# PCB.net
KiCad netlist of a schematic drawn in EasyEDA Pro
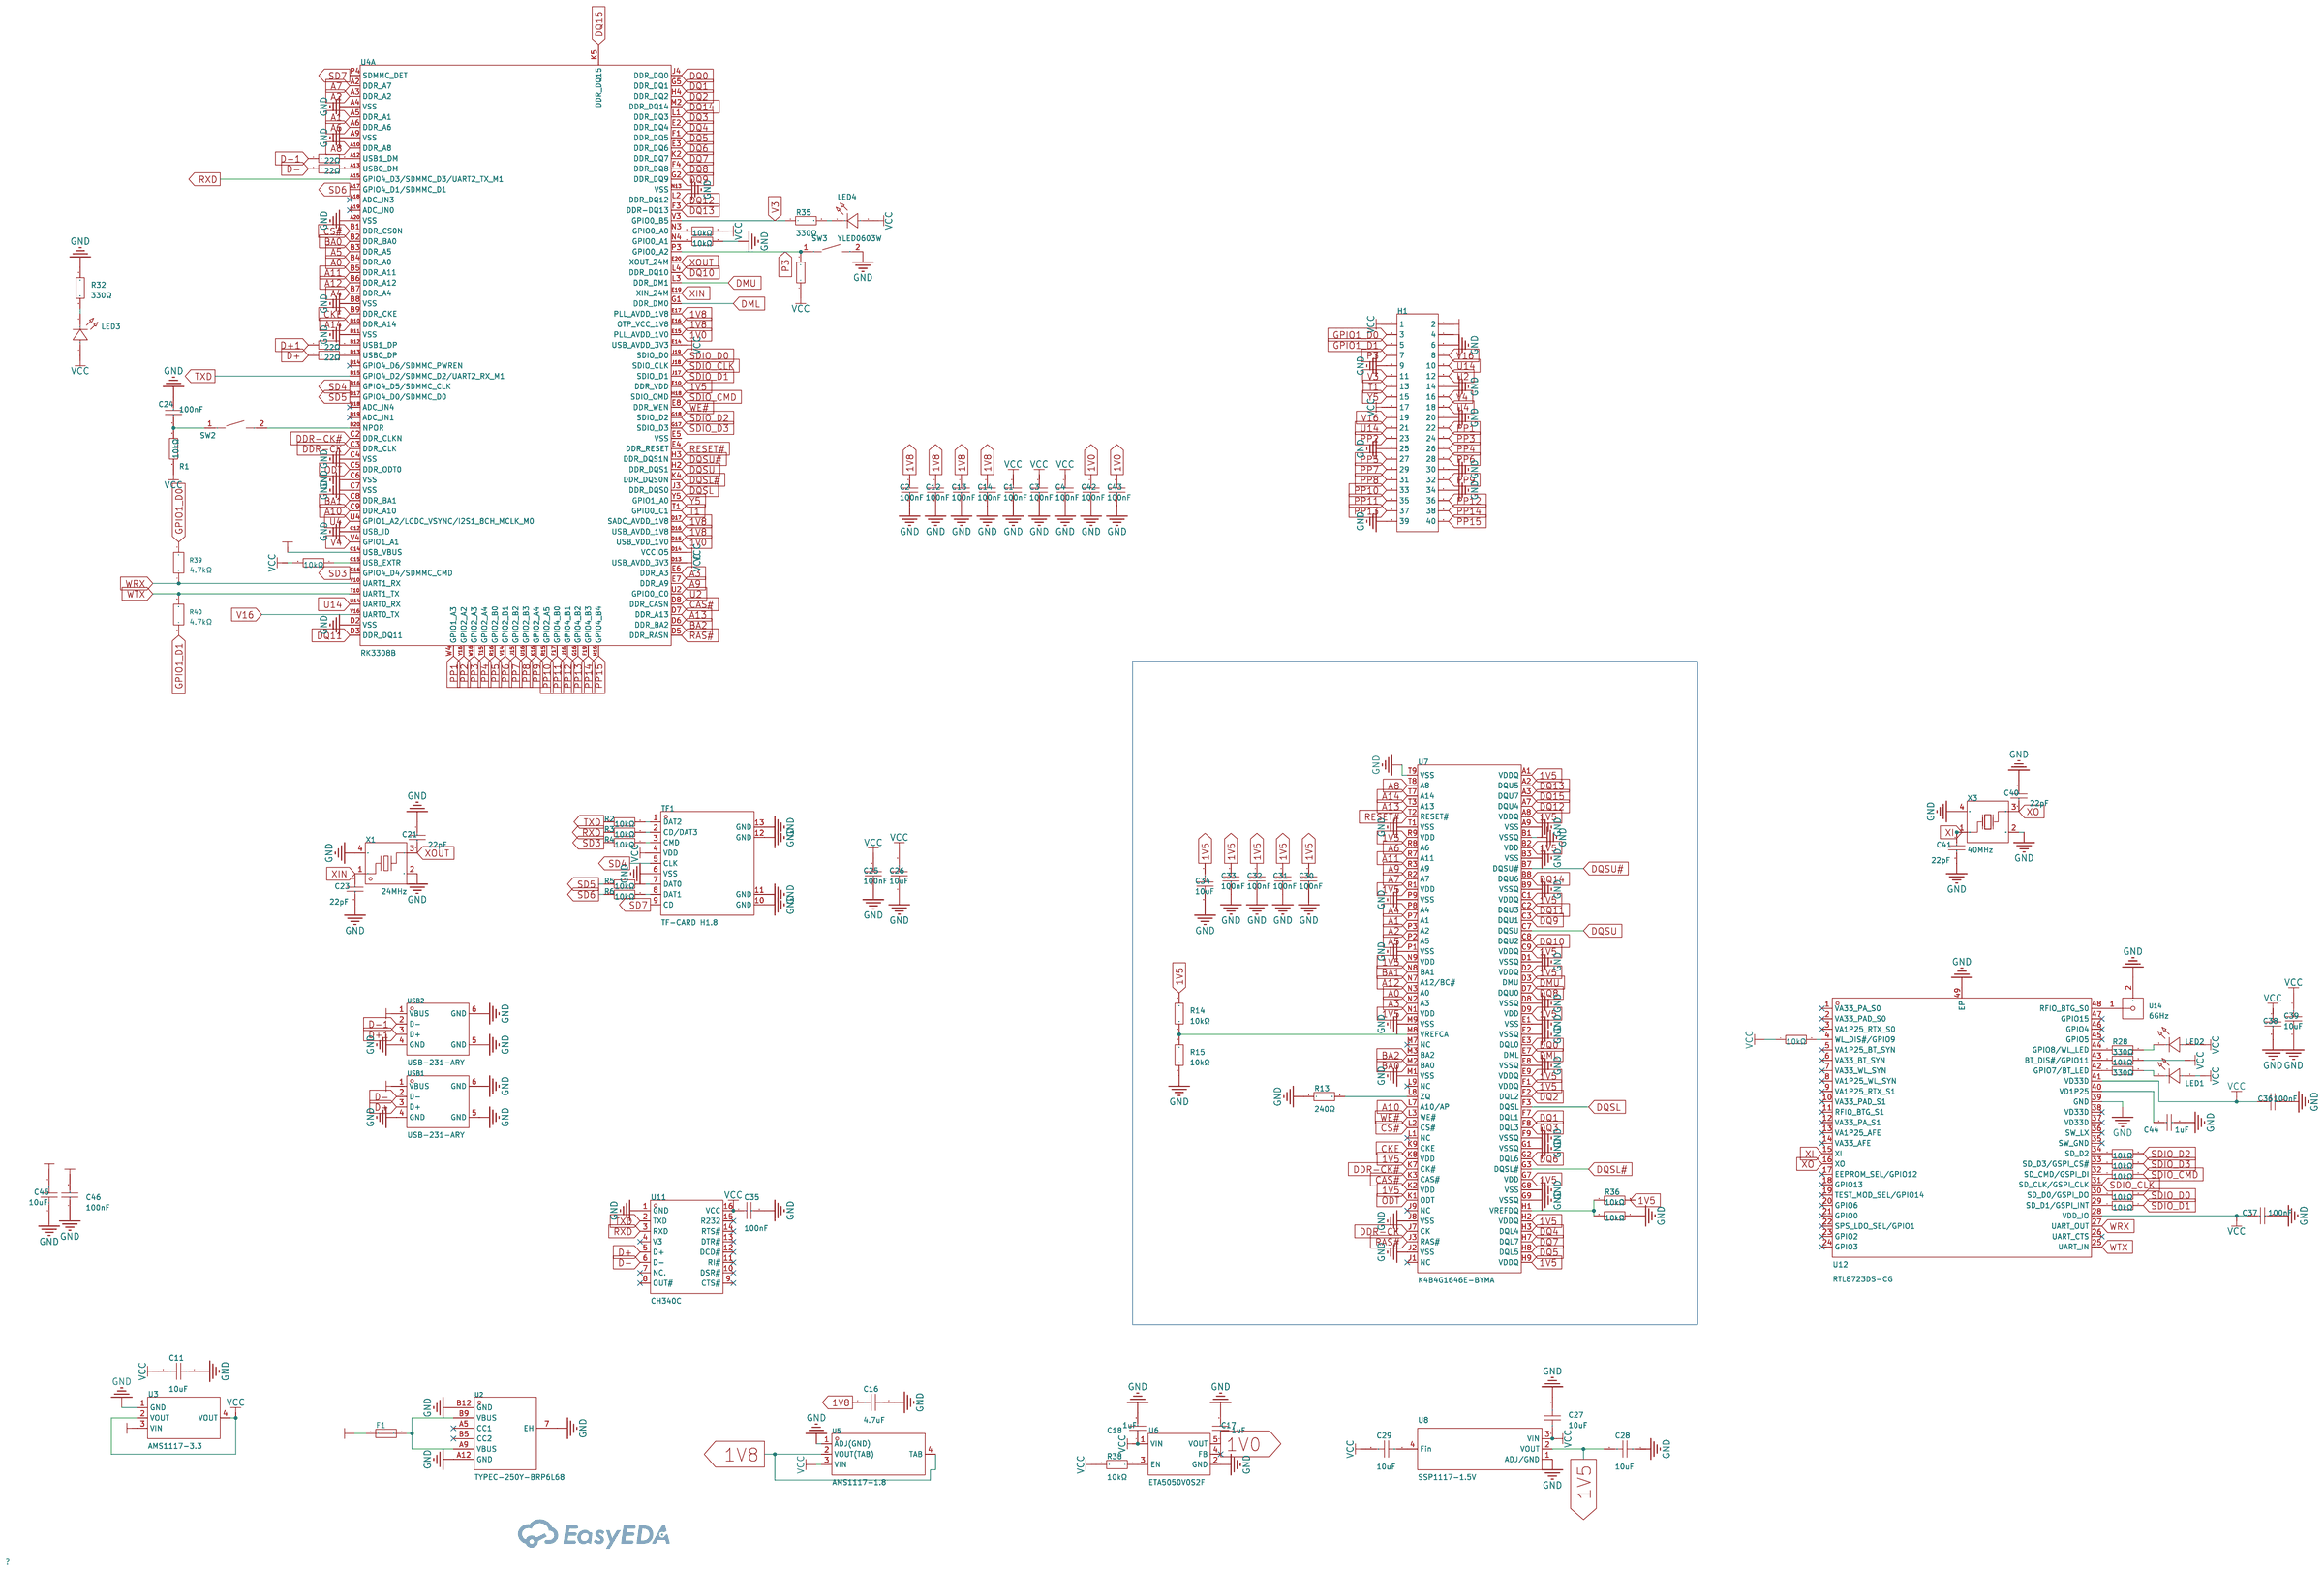
[diagram p0: schematic sheet]

(export (version "E")
  (design (tool "Eeschema 10.0.6"))
  (components
    (comp (ref "C1")
      (value "100nF")
      (footprint "easyedapro:C0603")
      (description "Capacitance:100nF Tolerance:±10% Tolerance:±10% Voltage Rating:50V Temperature Coefficient:-")
      (fields
        (field (name "Manufacturer Part") "CT41G-0603-2X1-50V-0.1uF-K(N)")
        (field (name "Manufacturer") "TORCH(火炬)")
      )
      (libsource (lib "easyedapro") (part "CT41G-0603-2X1-50V-0.1μF-K(N)"))
    )
    (comp (ref "C2")
      (value "100nF")
      (footprint "easyedapro:C0603")
      (description "Capacitance:100nF Tolerance:±10% Tolerance:±10% Voltage Rating:50V Temperature Coefficient:-")
      (fields
        (field (name "Manufacturer Part") "CT41G-0603-2X1-50V-0.1uF-K(N)")
        (field (name "Manufacturer") "TORCH(火炬)")
      )
      (libsource (lib "easyedapro") (part "CT41G-0603-2X1-50V-0.1μF-K(N)"))
    )
    (comp (ref "C3")
      (value "100nF")
      (footprint "easyedapro:C0603")
      (description "Capacitance:100nF Tolerance:±10% Tolerance:±10% Voltage Rating:50V Temperature Coefficient:-")
      (fields
        (field (name "Manufacturer Part") "CT41G-0603-2X1-50V-0.1uF-K(N)")
        (field (name "Manufacturer") "TORCH(火炬)")
      )
      (libsource (lib "easyedapro") (part "CT41G-0603-2X1-50V-0.1μF-K(N)"))
    )
    (comp (ref "C4")
      (value "100nF")
      (footprint "easyedapro:C0603")
      (description "Capacitance:100nF Tolerance:±10% Tolerance:±10% Voltage Rating:50V Temperature Coefficient:-")
      (fields
        (field (name "Manufacturer Part") "CT41G-0603-2X1-50V-0.1uF-K(N)")
        (field (name "Manufacturer") "TORCH(火炬)")
      )
      (libsource (lib "easyedapro") (part "CT41G-0603-2X1-50V-0.1μF-K(N)"))
    )
    (comp (ref "C11")
      (value "10uF")
      (footprint "easyedapro:C0603")
      (description "Capacitance:10uF Tolerance:±10% Tolerance:±10% Voltage Rating:10V Temperature Coefficient:X5R")
      (fields
        (field (name "Manufacturer Part") "CL10A106KP8NNNC")
        (field (name "Manufacturer") "SAMSUNG(三星)")
      )
      (libsource (lib "easyedapro") (part "CL10A106KP8NNNC"))
    )
    (comp (ref "C12")
      (value "100nF")
      (footprint "easyedapro:C0603")
      (description "Capacitance:100nF Tolerance:±10% Tolerance:±10% Voltage Rating:50V Temperature Coefficient:-")
      (fields
        (field (name "Manufacturer Part") "CT41G-0603-2X1-50V-0.1uF-K(N)")
        (field (name "Manufacturer") "TORCH(火炬)")
      )
      (libsource (lib "easyedapro") (part "CT41G-0603-2X1-50V-0.1μF-K(N)"))
    )
    (comp (ref "C13")
      (value "100nF")
      (footprint "easyedapro:C0603")
      (description "Capacitance:100nF Tolerance:±10% Tolerance:±10% Voltage Rating:50V Temperature Coefficient:-")
      (fields
        (field (name "Manufacturer Part") "CT41G-0603-2X1-50V-0.1uF-K(N)")
        (field (name "Manufacturer") "TORCH(火炬)")
      )
      (libsource (lib "easyedapro") (part "CT41G-0603-2X1-50V-0.1μF-K(N)"))
    )
    (comp (ref "C14")
      (value "100nF")
      (footprint "easyedapro:C0603")
      (description "Capacitance:100nF Tolerance:±10% Tolerance:±10% Voltage Rating:50V Temperature Coefficient:-")
      (fields
        (field (name "Manufacturer Part") "CT41G-0603-2X1-50V-0.1uF-K(N)")
        (field (name "Manufacturer") "TORCH(火炬)")
      )
      (libsource (lib "easyedapro") (part "CT41G-0603-2X1-50V-0.1μF-K(N)"))
    )
    (comp (ref "C16")
      (value "4.7uF")
      (footprint "easyedapro:C0603")
      (description "Capacitance:4.7uF Tolerance:±10% Tolerance:±10% Voltage Rating:16V Temperature Coefficient:X5R")
      (fields
        (field (name "Manufacturer Part") "CL10A475KO8NNNC")
        (field (name "Manufacturer") "SAMSUNG(三星)")
      )
      (libsource (lib "easyedapro") (part "CL10A475KO8NNNC"))
    )
    (comp (ref "C17")
      (value "1uF")
      (footprint "easyedapro:C0603")
      (description "Capacitance:1uF Tolerance:±10% Tolerance:±10% Voltage Rating:25V Temperature Coefficient:X7R")
      (fields
        (field (name "Manufacturer Part") "CL10B105KA8NNNC")
        (field (name "Manufacturer") "SAMSUNG(三星)")
      )
      (libsource (lib "easyedapro") (part "CL10B105KA8NNNC"))
    )
    (comp (ref "C18")
      (value "1uF")
      (footprint "easyedapro:C0603")
      (description "Capacitance:1uF Tolerance:±10% Tolerance:±10% Voltage Rating:25V Temperature Coefficient:X7R")
      (fields
        (field (name "Manufacturer Part") "CL10B105KA8NNNC")
        (field (name "Manufacturer") "SAMSUNG(三星)")
      )
      (libsource (lib "easyedapro") (part "CL10B105KA8NNNC"))
    )
    (comp (ref "C21")
      (value "22pF")
      (footprint "easyedapro:C0603")
      (description "Capacitance:22pF Tolerance:±5% Tolerance:±5% Voltage Rating:50V Temperature Coefficient:C0G")
      (fields
        (field (name "Manufacturer Part") "CL10C220JB8NNNC")
        (field (name "Manufacturer") "SAMSUNG(三星)")
      )
      (libsource (lib "easyedapro") (part "CL10C220JB8NNNC"))
    )
    (comp (ref "C23")
      (value "22pF")
      (footprint "easyedapro:C0603")
      (description "Capacitance:22pF Tolerance:±5% Tolerance:±5% Voltage Rating:50V Temperature Coefficient:C0G")
      (fields
        (field (name "Manufacturer Part") "CL10C220JB8NNNC")
        (field (name "Manufacturer") "SAMSUNG(三星)")
      )
      (libsource (lib "easyedapro") (part "CL10C220JB8NNNC"))
    )
    (comp (ref "C24")
      (value "100nF")
      (footprint "easyedapro:C0603")
      (description "Capacitance:100nF Tolerance:±10% Tolerance:±10% Voltage Rating:50V Temperature Coefficient:-")
      (fields
        (field (name "Manufacturer Part") "CT41G-0603-2X1-50V-0.1uF-K(N)")
        (field (name "Manufacturer") "TORCH(火炬)")
      )
      (libsource (lib "easyedapro") (part "CT41G-0603-2X1-50V-0.1μF-K(N)"))
    )
    (comp (ref "C25")
      (value "100nF")
      (footprint "easyedapro:C0603")
      (description "Capacitance:100nF Tolerance:±10% Tolerance:±10% Voltage Rating:50V Temperature Coefficient:-")
      (fields
        (field (name "Manufacturer Part") "CT41G-0603-2X1-50V-0.1uF-K(N)")
        (field (name "Manufacturer") "TORCH(火炬)")
      )
      (libsource (lib "easyedapro") (part "CT41G-0603-2X1-50V-0.1μF-K(N)"))
    )
    (comp (ref "C26")
      (value "10uF")
      (footprint "easyedapro:C0603")
      (description "Capacitance:10uF Tolerance:±10% Tolerance:±10% Voltage Rating:10V Temperature Coefficient:X5R")
      (fields
        (field (name "Manufacturer Part") "CL10A106KP8NNNC")
        (field (name "Manufacturer") "SAMSUNG(三星)")
      )
      (libsource (lib "easyedapro") (part "CL10A106KP8NNNC"))
    )
    (comp (ref "C27")
      (value "10uF")
      (footprint "easyedapro:C0603")
      (description "Capacitance:10uF Tolerance:±10% Tolerance:±10% Voltage Rating:10V Temperature Coefficient:X5R")
      (fields
        (field (name "Manufacturer Part") "CL10A106KP8NNNC")
        (field (name "Manufacturer") "SAMSUNG(三星)")
      )
      (libsource (lib "easyedapro") (part "CL10A106KP8NNNC"))
    )
    (comp (ref "C28")
      (value "10uF")
      (footprint "easyedapro:C0603")
      (description "Capacitance:10uF Tolerance:±10% Tolerance:±10% Voltage Rating:10V Temperature Coefficient:X5R")
      (fields
        (field (name "Manufacturer Part") "CL10A106KP8NNNC")
        (field (name "Manufacturer") "SAMSUNG(三星)")
      )
      (libsource (lib "easyedapro") (part "CL10A106KP8NNNC"))
    )
    (comp (ref "C29")
      (value "10uF")
      (footprint "easyedapro:C0603")
      (description "Capacitance:10uF Tolerance:±10% Tolerance:±10% Voltage Rating:10V Temperature Coefficient:X5R")
      (fields
        (field (name "Manufacturer Part") "CL10A106KP8NNNC")
        (field (name "Manufacturer") "SAMSUNG(三星)")
      )
      (libsource (lib "easyedapro") (part "CL10A106KP8NNNC"))
    )
    (comp (ref "C30")
      (value "100nF")
      (footprint "easyedapro:C0603")
      (description "Capacitance:100nF Tolerance:±10% Tolerance:±10% Voltage Rating:50V Temperature Coefficient:-")
      (fields
        (field (name "Manufacturer Part") "CT41G-0603-2X1-50V-0.1uF-K(N)")
        (field (name "Manufacturer") "TORCH(火炬)")
      )
      (libsource (lib "easyedapro") (part "CT41G-0603-2X1-50V-0.1μF-K(N)"))
    )
    (comp (ref "C31")
      (value "100nF")
      (footprint "easyedapro:C0603")
      (description "Capacitance:100nF Tolerance:±10% Tolerance:±10% Voltage Rating:50V Temperature Coefficient:-")
      (fields
        (field (name "Manufacturer Part") "CT41G-0603-2X1-50V-0.1uF-K(N)")
        (field (name "Manufacturer") "TORCH(火炬)")
      )
      (libsource (lib "easyedapro") (part "CT41G-0603-2X1-50V-0.1μF-K(N)"))
    )
    (comp (ref "C32")
      (value "100nF")
      (footprint "easyedapro:C0603")
      (description "Capacitance:100nF Tolerance:±10% Tolerance:±10% Voltage Rating:50V Temperature Coefficient:-")
      (fields
        (field (name "Manufacturer Part") "CT41G-0603-2X1-50V-0.1uF-K(N)")
        (field (name "Manufacturer") "TORCH(火炬)")
      )
      (libsource (lib "easyedapro") (part "CT41G-0603-2X1-50V-0.1μF-K(N)"))
    )
    (comp (ref "C33")
      (value "100nF")
      (footprint "easyedapro:C0603")
      (description "Capacitance:100nF Tolerance:±10% Tolerance:±10% Voltage Rating:50V Temperature Coefficient:-")
      (fields
        (field (name "Manufacturer Part") "CT41G-0603-2X1-50V-0.1uF-K(N)")
        (field (name "Manufacturer") "TORCH(火炬)")
      )
      (libsource (lib "easyedapro") (part "CT41G-0603-2X1-50V-0.1μF-K(N)"))
    )
    (comp (ref "C34")
      (value "10uF")
      (footprint "easyedapro:C0603")
      (description "Capacitance:10uF Tolerance:±10% Tolerance:±10% Voltage Rating:10V Temperature Coefficient:X5R")
      (fields
        (field (name "Manufacturer Part") "CL10A106KP8NNNC")
        (field (name "Manufacturer") "SAMSUNG(三星)")
      )
      (libsource (lib "easyedapro") (part "CL10A106KP8NNNC"))
    )
    (comp (ref "C35")
      (value "100nF")
      (footprint "easyedapro:C0603")
      (description "Capacitance:100nF Tolerance:±10% Tolerance:±10% Voltage Rating:50V Temperature Coefficient:-")
      (fields
        (field (name "Manufacturer Part") "CT41G-0603-2X1-50V-0.1uF-K(N)")
        (field (name "Manufacturer") "TORCH(火炬)")
      )
      (libsource (lib "easyedapro") (part "CT41G-0603-2X1-50V-0.1μF-K(N)"))
    )
    (comp (ref "C36")
      (value "100nF")
      (footprint "easyedapro:C0603")
      (description "Capacitance:100nF Tolerance:±10% Tolerance:±10% Voltage Rating:50V Temperature Coefficient:-")
      (fields
        (field (name "Manufacturer Part") "CT41G-0603-2X1-50V-0.1uF-K(N)")
        (field (name "Manufacturer") "TORCH(火炬)")
      )
      (libsource (lib "easyedapro") (part "CT41G-0603-2X1-50V-0.1μF-K(N)"))
    )
    (comp (ref "C37")
      (value "100nF")
      (footprint "easyedapro:C0603")
      (description "Capacitance:100nF Tolerance:±10% Tolerance:±10% Voltage Rating:50V Temperature Coefficient:-")
      (fields
        (field (name "Manufacturer Part") "CT41G-0603-2X1-50V-0.1uF-K(N)")
        (field (name "Manufacturer") "TORCH(火炬)")
      )
      (libsource (lib "easyedapro") (part "CT41G-0603-2X1-50V-0.1μF-K(N)"))
    )
    (comp (ref "C38")
      (value "100nF")
      (footprint "easyedapro:C0603")
      (description "Capacitance:100nF Tolerance:±10% Tolerance:±10% Voltage Rating:50V Temperature Coefficient:-")
      (fields
        (field (name "Manufacturer Part") "CT41G-0603-2X1-50V-0.1uF-K(N)")
        (field (name "Manufacturer") "TORCH(火炬)")
      )
      (libsource (lib "easyedapro") (part "CT41G-0603-2X1-50V-0.1μF-K(N)"))
    )
    (comp (ref "C39")
      (value "10uF")
      (footprint "easyedapro:C0603")
      (description "Capacitance:10uF Tolerance:±10% Tolerance:±10% Voltage Rating:10V Temperature Coefficient:X5R")
      (fields
        (field (name "Manufacturer Part") "CL10A106KP8NNNC")
        (field (name "Manufacturer") "SAMSUNG(三星)")
      )
      (libsource (lib "easyedapro") (part "CL10A106KP8NNNC"))
    )
    (comp (ref "C40")
      (value "22pF")
      (footprint "easyedapro:C0603")
      (description "Capacitance:22pF Tolerance:±5% Tolerance:±5% Voltage Rating:50V Temperature Coefficient:C0G")
      (fields
        (field (name "Manufacturer Part") "CL10C220JB8NNNC")
        (field (name "Manufacturer") "SAMSUNG(三星)")
      )
      (libsource (lib "easyedapro") (part "CL10C220JB8NNNC"))
    )
    (comp (ref "C41")
      (value "22pF")
      (footprint "easyedapro:C0603")
      (description "Capacitance:22pF Tolerance:±5% Tolerance:±5% Voltage Rating:50V Temperature Coefficient:C0G")
      (fields
        (field (name "Manufacturer Part") "CL10C220JB8NNNC")
        (field (name "Manufacturer") "SAMSUNG(三星)")
      )
      (libsource (lib "easyedapro") (part "CL10C220JB8NNNC"))
    )
    (comp (ref "C42")
      (value "100nF")
      (footprint "easyedapro:C0603")
      (description "Capacitance:100nF Tolerance:±10% Tolerance:±10% Voltage Rating:50V Temperature Coefficient:-")
      (fields
        (field (name "Manufacturer Part") "CT41G-0603-2X1-50V-0.1uF-K(N)")
        (field (name "Manufacturer") "TORCH(火炬)")
      )
      (libsource (lib "easyedapro") (part "CT41G-0603-2X1-50V-0.1μF-K(N)"))
    )
    (comp (ref "C43")
      (value "100nF")
      (footprint "easyedapro:C0603")
      (description "Capacitance:100nF Tolerance:±10% Tolerance:±10% Voltage Rating:50V Temperature Coefficient:-")
      (fields
        (field (name "Manufacturer Part") "CT41G-0603-2X1-50V-0.1uF-K(N)")
        (field (name "Manufacturer") "TORCH(火炬)")
      )
      (libsource (lib "easyedapro") (part "CT41G-0603-2X1-50V-0.1μF-K(N)"))
    )
    (comp (ref "C44")
      (value "1uF")
      (footprint "easyedapro:C0603")
      (description "Capacitance:1uF Tolerance:±10% Tolerance:±10% Voltage Rating:25V Temperature Coefficient:X7R")
      (fields
        (field (name "Manufacturer Part") "CL10B105KA8NNNC")
        (field (name "Manufacturer") "SAMSUNG(三星)")
      )
      (libsource (lib "easyedapro") (part "CL10B105KA8NNNC"))
    )
    (comp (ref "C45")
      (value "10uF")
      (footprint "easyedapro:C0603")
      (description "Capacitance:10uF Tolerance:±10% Tolerance:±10% Voltage Rating:10V Temperature Coefficient:X5R")
      (fields
        (field (name "Manufacturer Part") "CL10A106KP8NNNC")
        (field (name "Manufacturer") "SAMSUNG(三星)")
      )
      (libsource (lib "easyedapro") (part "CL10A106KP8NNNC"))
    )
    (comp (ref "C46")
      (value "100nF")
      (footprint "easyedapro:C0603")
      (description "Capacitance:100nF Tolerance:±10% Tolerance:±10% Voltage Rating:50V Temperature Coefficient:-")
      (fields
        (field (name "Manufacturer Part") "CT41G-0603-2X1-50V-0.1uF-K(N)")
        (field (name "Manufacturer") "TORCH(火炬)")
      )
      (libsource (lib "easyedapro") (part "CT41G-0603-2X1-50V-0.1μF-K(N)"))
    )
    (comp (ref "F1")
      (value "MINISMDC050F-2")
      (footprint "easyedapro:F1812")
      (fields (field (name "Manufacturer") "Littelfuse(美国力特)"))
      (libsource (lib "easyedapro") (part "MINISMDC050F-2"))
    )
    (comp (ref "H1")
      (value "2.54mm 2*20P直排针")
      (footprint "easyedapro:HDR-TH_40P-P2.54-V-M-R2-C20-S2.54")
      (fields (field (name "Manufacturer") "BOOMELE(博穆精密)"))
      (libsource (lib "easyedapro") (part "Header-Male-2.54_2x20"))
    )
    (comp (ref "LED1")
      (value "XL-1608UBC-04")
      (footprint "easyedapro:LED0603-RD_BLUE")
      (fields (field (name "Manufacturer") "XINGLIGHT(成兴光)"))
      (libsource (lib "easyedapro") (part "XL-1608UBC-04"))
    )
    (comp (ref "LED2")
      (value "19-219/GHC-YR2T1B5Y/3T")
      (footprint "easyedapro:LED-SMD_L1.6-W0.8_19-219-GHC-YR2T1B5Y-3T")
      (fields (field (name "Manufacturer") "EVERLIGHT(亿光)"))
      (libsource (lib "easyedapro") (part "19-219/GHC-YR2T1B5Y/3T"))
    )
    (comp (ref "LED3")
      (value "19-219/GHC-YR2T1B5Y/3T")
      (footprint "easyedapro:LED-SMD_L1.6-W0.8_19-219-GHC-YR2T1B5Y-3T")
      (fields (field (name "Manufacturer") "EVERLIGHT(亿光)"))
      (libsource (lib "easyedapro") (part "19-219/GHC-YR2T1B5Y/3T"))
    )
    (comp (ref "LED4")
      (value "YLED0603W")
      (footprint "easyedapro:LED0603-RD")
      (fields (field (name "Manufacturer") "YONGYUTAI(永裕泰)"))
      (libsource (lib "easyedapro") (part "YLED0603W"))
    )
    (comp (ref "R1")
      (value "10kΩ")
      (footprint "easyedapro:R0603")
      (fields (field (name "Manufacturer Part") "RC0603FR-0710KL") (field (name "Manufacturer") "YAGEO(国巨)"))
      (libsource (lib "easyedapro") (part "RC0603FR-0710KL"))
    )
    (comp (ref "R2")
      (value "10kΩ")
      (footprint "easyedapro:R0603")
      (fields (field (name "Manufacturer Part") "RC0603FR-0710KL") (field (name "Manufacturer") "YAGEO(国巨)"))
      (libsource (lib "easyedapro") (part "RC0603FR-0710KL"))
    )
    (comp (ref "R3")
      (value "10kΩ")
      (footprint "easyedapro:R0603")
      (fields (field (name "Manufacturer Part") "RC0603FR-0710KL") (field (name "Manufacturer") "YAGEO(国巨)"))
      (libsource (lib "easyedapro") (part "RC0603FR-0710KL"))
    )
    (comp (ref "R4")
      (value "10kΩ")
      (footprint "easyedapro:R0603")
      (fields (field (name "Manufacturer Part") "RC0603FR-0710KL") (field (name "Manufacturer") "YAGEO(国巨)"))
      (libsource (lib "easyedapro") (part "RC0603FR-0710KL"))
    )
    (comp (ref "R5")
      (value "10kΩ")
      (footprint "easyedapro:R0603")
      (fields (field (name "Manufacturer Part") "RC0603FR-0710KL") (field (name "Manufacturer") "YAGEO(国巨)"))
      (libsource (lib "easyedapro") (part "RC0603FR-0710KL"))
    )
    (comp (ref "R6")
      (value "10kΩ")
      (footprint "easyedapro:R0603")
      (fields (field (name "Manufacturer Part") "RC0603FR-0710KL") (field (name "Manufacturer") "YAGEO(国巨)"))
      (libsource (lib "easyedapro") (part "RC0603FR-0710KL"))
    )
    (comp (ref "R13")
      (value "240Ω")
      (footprint "easyedapro:R0603")
      (fields (field (name "Manufacturer Part") "RC0603FR-07240RL") (field (name "Manufacturer") "YAGEO(国巨)"))
      (libsource (lib "easyedapro") (part "RC0603FR-07240RL"))
    )
    (comp (ref "R14")
      (value "10kΩ")
      (footprint "easyedapro:R0603")
      (fields (field (name "Manufacturer Part") "RC0603FR-0710KL") (field (name "Manufacturer") "YAGEO(国巨)"))
      (libsource (lib "easyedapro") (part "RC0603FR-0710KL"))
    )
    (comp (ref "R15")
      (value "10kΩ")
      (footprint "easyedapro:R0603")
      (fields (field (name "Manufacturer Part") "RC0603FR-0710KL") (field (name "Manufacturer") "YAGEO(国巨)"))
      (libsource (lib "easyedapro") (part "RC0603FR-0710KL"))
    )
    (comp (ref "R17")
      (value "22Ω")
      (footprint "easyedapro:R0603")
      (fields
        (field (name "Manufacturer Part") "0603WAF220JT5E")
        (field (name "Manufacturer") "UNI-ROYAL(厚声)")
      )
      (libsource (lib "easyedapro") (part "0603WAF220JT5E"))
    )
    (comp (ref "R18")
      (value "22Ω")
      (footprint "easyedapro:R0603")
      (fields
        (field (name "Manufacturer Part") "0603WAF220JT5E")
        (field (name "Manufacturer") "UNI-ROYAL(厚声)")
      )
      (libsource (lib "easyedapro") (part "0603WAF220JT5E"))
    )
    (comp (ref "R19")
      (value "22Ω")
      (footprint "easyedapro:R0603")
      (fields
        (field (name "Manufacturer Part") "0603WAF220JT5E")
        (field (name "Manufacturer") "UNI-ROYAL(厚声)")
      )
      (libsource (lib "easyedapro") (part "0603WAF220JT5E"))
    )
    (comp (ref "R20")
      (value "22Ω")
      (footprint "easyedapro:R0603")
      (fields
        (field (name "Manufacturer Part") "0603WAF220JT5E")
        (field (name "Manufacturer") "UNI-ROYAL(厚声)")
      )
      (libsource (lib "easyedapro") (part "0603WAF220JT5E"))
    )
    (comp (ref "R21")
      (value "10kΩ")
      (footprint "easyedapro:R0603")
      (fields (field (name "Manufacturer Part") "RC0603FR-0710KL") (field (name "Manufacturer") "YAGEO(国巨)"))
      (libsource (lib "easyedapro") (part "RC0603FR-0710KL"))
    )
    (comp (ref "R22")
      (value "10kΩ")
      (footprint "easyedapro:R0603")
      (fields (field (name "Manufacturer Part") "RC0603FR-0710KL") (field (name "Manufacturer") "YAGEO(国巨)"))
      (libsource (lib "easyedapro") (part "RC0603FR-0710KL"))
    )
    (comp (ref "R23")
      (value "10kΩ")
      (footprint "easyedapro:R0603")
      (fields (field (name "Manufacturer Part") "RC0603FR-0710KL") (field (name "Manufacturer") "YAGEO(国巨)"))
      (libsource (lib "easyedapro") (part "RC0603FR-0710KL"))
    )
    (comp (ref "R24")
      (value "10kΩ")
      (footprint "easyedapro:R0603")
      (fields (field (name "Manufacturer Part") "RC0603FR-0710KL") (field (name "Manufacturer") "YAGEO(国巨)"))
      (libsource (lib "easyedapro") (part "RC0603FR-0710KL"))
    )
    (comp (ref "R25")
      (value "10kΩ")
      (footprint "easyedapro:R0603")
      (fields (field (name "Manufacturer Part") "RC0603FR-0710KL") (field (name "Manufacturer") "YAGEO(国巨)"))
      (libsource (lib "easyedapro") (part "RC0603FR-0710KL"))
    )
    (comp (ref "R26")
      (value "10kΩ")
      (footprint "easyedapro:R0603")
      (fields (field (name "Manufacturer Part") "RC0603FR-0710KL") (field (name "Manufacturer") "YAGEO(国巨)"))
      (libsource (lib "easyedapro") (part "RC0603FR-0710KL"))
    )
    (comp (ref "R27")
      (value "10kΩ")
      (footprint "easyedapro:R0603")
      (fields (field (name "Manufacturer Part") "RC0603FR-0710KL") (field (name "Manufacturer") "YAGEO(国巨)"))
      (libsource (lib "easyedapro") (part "RC0603FR-0710KL"))
    )
    (comp (ref "R28")
      (value "330Ω")
      (footprint "easyedapro:R0603")
      (fields (field (name "Manufacturer Part") "RC0603FR-07330RL") (field (name "Manufacturer") "YAGEO(国巨)"))
      (libsource (lib "easyedapro") (part "RC0603FR-07330RL"))
    )
    (comp (ref "R29")
      (value "330Ω")
      (footprint "easyedapro:R0603")
      (fields (field (name "Manufacturer Part") "RC0603FR-07330RL") (field (name "Manufacturer") "YAGEO(国巨)"))
      (libsource (lib "easyedapro") (part "RC0603FR-07330RL"))
    )
    (comp (ref "R30")
      (value "10kΩ")
      (footprint "easyedapro:R0603")
      (fields (field (name "Manufacturer Part") "RC0603FR-0710KL") (field (name "Manufacturer") "YAGEO(国巨)"))
      (libsource (lib "easyedapro") (part "RC0603FR-0710KL"))
    )
    (comp (ref "R31")
      (value "10kΩ")
      (footprint "easyedapro:R0603")
      (fields (field (name "Manufacturer Part") "RC0603FR-0710KL") (field (name "Manufacturer") "YAGEO(国巨)"))
      (libsource (lib "easyedapro") (part "RC0603FR-0710KL"))
    )
    (comp (ref "R32")
      (value "330Ω")
      (footprint "easyedapro:R0603")
      (fields (field (name "Manufacturer Part") "RC0603FR-07330RL") (field (name "Manufacturer") "YAGEO(国巨)"))
      (libsource (lib "easyedapro") (part "RC0603FR-07330RL"))
    )
    (comp (ref "R33")
      (value "10kΩ")
      (footprint "easyedapro:R0603")
      (fields (field (name "Manufacturer Part") "RC0603FR-0710KL") (field (name "Manufacturer") "YAGEO(国巨)"))
      (libsource (lib "easyedapro") (part "RC0603FR-0710KL"))
    )
    (comp (ref "R34")
      (value "10kΩ")
      (footprint "easyedapro:R0603")
      (fields (field (name "Manufacturer Part") "RC0603FR-0710KL") (field (name "Manufacturer") "YAGEO(国巨)"))
      (libsource (lib "easyedapro") (part "RC0603FR-0710KL"))
    )
    (comp (ref "R35")
      (value "330Ω")
      (footprint "easyedapro:R0603")
      (fields (field (name "Manufacturer Part") "RC0603FR-07330RL") (field (name "Manufacturer") "YAGEO(国巨)"))
      (libsource (lib "easyedapro") (part "RC0603FR-07330RL"))
    )
    (comp (ref "R36")
      (value "10kΩ")
      (footprint "easyedapro:R0603")
      (fields (field (name "Manufacturer Part") "RC0603FR-0710KL") (field (name "Manufacturer") "YAGEO(国巨)"))
      (libsource (lib "easyedapro") (part "RC0603FR-0710KL"))
    )
    (comp (ref "R37")
      (value "10kΩ")
      (footprint "easyedapro:R0603")
      (fields (field (name "Manufacturer Part") "RC0603FR-0710KL") (field (name "Manufacturer") "YAGEO(国巨)"))
      (libsource (lib "easyedapro") (part "RC0603FR-0710KL"))
    )
    (comp (ref "R38")
      (value "10kΩ")
      (footprint "easyedapro:R0603")
      (fields (field (name "Manufacturer Part") "RC0603FR-0710KL") (field (name "Manufacturer") "YAGEO(国巨)"))
      (libsource (lib "easyedapro") (part "RC0603FR-0710KL"))
    )
    (comp (ref "R39")
      (value "4.7kΩ")
      (footprint "easyedapro:R0603")
      (fields
        (field (name "Manufacturer Part") "HoLTT0603-1/10W-4.7K-1%")
        (field (name "Manufacturer") "Milliohm(毫欧)")
      )
      (libsource (lib "easyedapro") (part "HOLTT0603-1/10W-4.7K-1%"))
    )
    (comp (ref "R40")
      (value "4.7kΩ")
      (footprint "easyedapro:R0603")
      (fields
        (field (name "Manufacturer Part") "HoLTT0603-1/10W-4.7K-1%")
        (field (name "Manufacturer") "Milliohm(毫欧)")
      )
      (libsource (lib "easyedapro") (part "HOLTT0603-1/10W-4.7K-1%"))
    )
    (comp (ref "SW2")
      (value "TS-1088-AR02016")
      (footprint "easyedapro:SW-SMD_L3.9-W3.0-P4.45")
      (fields (field (name "Manufacturer") "XUNPU(讯普)"))
      (libsource (lib "easyedapro") (part "TS-1088-AR02016"))
    )
    (comp (ref "SW3")
      (value "TS-1088-AR02016")
      (footprint "easyedapro:SW-SMD_L3.9-W3.0-P4.45")
      (fields (field (name "Manufacturer") "XUNPU(讯普)"))
      (libsource (lib "easyedapro") (part "TS-1088-AR02016"))
    )
    (comp (ref "TF1")
      (value "TF-CARD H1.8")
      (footprint "easyedapro:TF-SMD_TF-CARD-H1.8")
      (fields (field (name "Manufacturer") "SHOU HAN(首韩)"))
      (libsource (lib "easyedapro") (part "TF-CARD H1.8"))
    )
    (comp (ref "U2")
      (value "TYPEC-250Y-BRP6L68")
      (footprint "easyedapro:TYPE-C-SMD_XUNPU_TYPEC-250Y-BRP6L68")
      (fields (field (name "Manufacturer") "XUNPU(讯普)"))
      (libsource (lib "easyedapro") (part "TYPEC-250Y-BRP6L68"))
    )
    (comp (ref "U3")
      (value "AMS1117-3.3")
      (footprint "easyedapro:SOT-223-3_L6.5-W3.4-P2.30-LS7.0-BR")
      (fields (field (name "Manufacturer") "AMS"))
      (libsource (lib "easyedapro") (part "AMS1117-3.3"))
    )
    (comp (ref "U4")
      (value "RK3308B")
      (footprint "easyedapro:BGA-355_L13.0-W13.0-P0.65_RK3308")
      (fields (field (name "Manufacturer") "Rockchip(瑞芯微)"))
      (libsource (lib "easyedapro") (part "RK3308B_C22447822"))
    )
    (comp (ref "U5")
      (value "AMS1117-1.8")
      (footprint "easyedapro:SOT-223_L6.5-W3.5-P2.30-LS7.0-BR")
      (fields (field (name "Manufacturer") "YONGYUTAI(永裕泰)"))
      (libsource (lib "easyedapro") (part "AMS1117-1.8_C2891837"))
    )
    (comp (ref "U6")
      (value "ETA5050V0S2F")
      (footprint "easyedapro:SOT-23-5_L3.0-W1.5-P0.95-LS2.8-BL")
      (fields (field (name "Manufacturer") "ETA(钰泰)"))
      (libsource (lib "easyedapro") (part "ETA5050V0S2F"))
    )
    (comp (ref "U7")
      (value "K4B4G1646E-BYMA")
      (footprint "easyedapro:FBGA-96_L13.5-W7.5-R16-C6-P0.80-TL")
      (fields (field (name "Manufacturer") "SAMSUNG(三星半导体)"))
      (libsource (lib "easyedapro") (part "K4B4G1646E-BYMA 4GB"))
    )
    (comp (ref "U8")
      (value "SSP1117-1.5V")
      (footprint "easyedapro:SOT-223_L6.3-W3.5-P2.30-LS7.0-BR")
      (fields (field (name "Manufacturer") "Siproin(上海矽朋)"))
      (libsource (lib "easyedapro") (part "SSP1117-1.5V"))
    )
    (comp (ref "U11")
      (value "CH340C")
      (footprint "easyedapro:SOP-16_L10.0-W3.9-P1.27-LS6.0-BL")
      (fields (field (name "Manufacturer") "WCH(南京沁恒)"))
      (libsource (lib "easyedapro") (part "CH340C"))
    )
    (comp (ref "U12")
      (value "RTL8723DS-CG")
      (footprint "easyedapro:WQFN-48_L6.0-W6.0-P0.40-BL-EP4.2")
      (fields (field (name "Manufacturer") "REALTEK(瑞昱)"))
      (libsource (lib "easyedapro") (part "RTL8723DS-CG"))
    )
    (comp (ref "U14")
      (value "6GHz")
      (footprint "easyedapro:IPEX-SMD_4P-L2.6-W2.6-LS3.0-1")
      (fields (field (name "Manufacturer Part") "RF-IPEX03-01") (field (name "Manufacturer") "DEALON(德艺隆)"))
      (libsource (lib "easyedapro") (part "RF-IPEX03-01"))
    )
    (comp (ref "USB1")
      (value "USB-231-ARY")
      (footprint "easyedapro:USB-A-TH_USB-231-ARY")
      (fields (field (name "Manufacturer") "XUNPU(讯普)"))
      (libsource (lib "easyedapro") (part "USB-231-ARY"))
    )
    (comp (ref "USB2")
      (value "USB-231-ARY")
      (footprint "easyedapro:USB-A-TH_USB-231-ARY")
      (fields (field (name "Manufacturer") "XUNPU(讯普)"))
      (libsource (lib "easyedapro") (part "USB-231-ARY"))
    )
    (comp (ref "X1")
      (value "24MHz")
      (footprint "easyedapro:CRYSTAL-SMD_4P-L3.2-W2.5-BL")
      (fields
        (field (name "Manufacturer Part") "XL2EL89COI-111YLC-24M")
        (field (name "Manufacturer") "YXC(扬兴晶振)")
      )
      (libsource (lib "easyedapro") (part "XL2EL89COI-111YLC-24M"))
    )
    (comp (ref "X3")
      (value "40MHz")
      (footprint "easyedapro:CRYSTAL-SMD_4P-L5.0-W3.2-BL")
      (fields
        (field (name "Manufacturer Part") "XVHEELNANF-40MHZ")
        (field (name "Manufacturer") "TAITIEN(泰艺电子)")
      )
      (libsource (lib "easyedapro") (part "XVHEELNANF-40MHZ"))
    )
  )
  (nets
    (net (code "1") (name "1V0") (class "Default")
      (node (ref "C17") (pin "1") (pinfunction "1_1") (pintype "input"))
      (node (ref "C42") (pin "1") (pinfunction "1_1") (pintype "input"))
      (node (ref "C43") (pin "1") (pinfunction "1_1") (pintype "input"))
      (node (ref "U4") (pin "D15") (pinfunction "USB_VDD_1V0_D15") (pintype "unspecified"))
      (node (ref "U4") (pin "E15") (pinfunction "PLL_AVDD_1V0_E15") (pintype "unspecified"))
      (node (ref "U6") (pin "5") (pinfunction "VOUT_5") (pintype "unspecified"))
    )
    (net (code "2") (name "1V5") (class "Default")
      (node (ref "C28") (pin "2") (pinfunction "2_2") (pintype "unspecified"))
      (node (ref "C30") (pin "1") (pinfunction "1_1") (pintype "input"))
      (node (ref "C31") (pin "1") (pinfunction "1_1") (pintype "input"))
      (node (ref "C32") (pin "1") (pinfunction "1_1") (pintype "input"))
      (node (ref "C33") (pin "1") (pinfunction "1_1") (pintype "input"))
      (node (ref "C34") (pin "1") (pinfunction "1_1") (pintype "unspecified"))
      (node (ref "R14") (pin "1") (pinfunction "1_1") (pintype "input"))
      (node (ref "R36") (pin "2") (pinfunction "2_2") (pintype "input"))
      (node (ref "U4") (pin "E10") (pinfunction "DDR_VDD_E10") (pintype "unspecified"))
      (node (ref "U7") (pin "A1") (pinfunction "VDDQ_A1") (pintype "unspecified"))
      (node (ref "U7") (pin "A8") (pinfunction "VDDQ_A8") (pintype "unspecified"))
      (node (ref "U7") (pin "B2") (pinfunction "VDD_B2") (pintype "unspecified"))
      (node (ref "U7") (pin "C1") (pinfunction "VDDQ_C1") (pintype "unspecified"))
      (node (ref "U7") (pin "C9") (pinfunction "VDDQ_C9") (pintype "unspecified"))
      (node (ref "U7") (pin "D2") (pinfunction "VDDQ_D2") (pintype "unspecified"))
      (node (ref "U7") (pin "D9") (pinfunction "VDD_D9") (pintype "unspecified"))
      (node (ref "U7") (pin "E9") (pinfunction "VDDQ_E9") (pintype "unspecified"))
      (node (ref "U7") (pin "F1") (pinfunction "VDDQ_F1") (pintype "unspecified"))
      (node (ref "U7") (pin "G7") (pinfunction "VDD_G7") (pintype "unspecified"))
      (node (ref "U7") (pin "H2") (pinfunction "VDDQ_H2") (pintype "unspecified"))
      (node (ref "U7") (pin "H9") (pinfunction "VDDQ_H9") (pintype "unspecified"))
      (node (ref "U7") (pin "K2") (pinfunction "VDD_K2") (pintype "unspecified"))
      (node (ref "U7") (pin "K8") (pinfunction "VDD_K8") (pintype "unspecified"))
      (node (ref "U7") (pin "N1") (pinfunction "VDD_N1") (pintype "unspecified"))
      (node (ref "U7") (pin "N9") (pinfunction "VDD_N9") (pintype "unspecified"))
      (node (ref "U7") (pin "R1") (pinfunction "VDD_R1") (pintype "unspecified"))
      (node (ref "U7") (pin "R9") (pinfunction "VDD_R9") (pintype "unspecified"))
      (node (ref "U8") (pin "2") (pinfunction "VOUT_2") (pintype "unspecified"))
    )
    (net (code "3") (name "1V8") (class "Default")
      (node (ref "C12") (pin "1") (pinfunction "1_1") (pintype "input"))
      (node (ref "C13") (pin "1") (pinfunction "1_1") (pintype "input"))
      (node (ref "C14") (pin "1") (pinfunction "1_1") (pintype "input"))
      (node (ref "C16") (pin "1") (pinfunction "1_1") (pintype "unspecified"))
      (node (ref "C2") (pin "1") (pinfunction "1_1") (pintype "input"))
      (node (ref "U4") (pin "D16") (pinfunction "USB_AVDD_1V8_D16") (pintype "unspecified"))
      (node (ref "U4") (pin "D17") (pinfunction "SADC_AVDD_1V8_D17") (pintype "unspecified"))
      (node (ref "U4") (pin "E16") (pinfunction "OTP_VCC_1V8_E16") (pintype "unspecified"))
      (node (ref "U4") (pin "E17") (pinfunction "PLL_AVDD_1V8_E17") (pintype "unspecified"))
      (node (ref "U5") (pin "2") (pinfunction "VOUT(TAB)_2") (pintype "input"))
      (node (ref "U5") (pin "4") (pinfunction "TAB_4") (pintype "input"))
    )
    (net (code "4") (name "A0") (class "Default")
      (node (ref "U4") (pin "B4") (pinfunction "DDR_A0_B4") (pintype "unspecified"))
      (node (ref "U7") (pin "N3") (pinfunction "A0_N3") (pintype "unspecified"))
    )
    (net (code "5") (name "A1") (class "Default")
      (node (ref "U4") (pin "A5") (pinfunction "DDR_A1_A5") (pintype "unspecified"))
      (node (ref "U7") (pin "P7") (pinfunction "A1_P7") (pintype "unspecified"))
    )
    (net (code "6") (name "A2") (class "Default")
      (node (ref "U4") (pin "A3") (pinfunction "DDR_A2_A3") (pintype "unspecified"))
      (node (ref "U7") (pin "P3") (pinfunction "A2_P3") (pintype "unspecified"))
    )
    (net (code "7") (name "A3") (class "Default")
      (node (ref "U4") (pin "E6") (pinfunction "DDR_A3_E6") (pintype "unspecified"))
      (node (ref "U7") (pin "N2") (pinfunction "A3_N2") (pintype "unspecified"))
    )
    (net (code "8") (name "A4") (class "Default")
      (node (ref "U4") (pin "B7") (pinfunction "DDR_A4_B7") (pintype "unspecified"))
      (node (ref "U7") (pin "P8") (pinfunction "A4_P8") (pintype "unspecified"))
    )
    (net (code "9") (name "A5") (class "Default")
      (node (ref "U4") (pin "B3") (pinfunction "DDR_A5_B3") (pintype "unspecified"))
      (node (ref "U7") (pin "P2") (pinfunction "A5_P2") (pintype "unspecified"))
    )
    (net (code "10") (name "A6") (class "Default")
      (node (ref "U4") (pin "A6") (pinfunction "DDR_A6_A6") (pintype "unspecified"))
      (node (ref "U7") (pin "R8") (pinfunction "A6_R8") (pintype "unspecified"))
    )
    (net (code "11") (name "A7") (class "Default")
      (node (ref "U4") (pin "A2") (pinfunction "DDR_A7_A2") (pintype "unspecified"))
      (node (ref "U7") (pin "R2") (pinfunction "A7_R2") (pintype "unspecified"))
    )
    (net (code "12") (name "A8") (class "Default")
      (node (ref "U4") (pin "A10") (pinfunction "DDR_A8_A10") (pintype "unspecified"))
      (node (ref "U7") (pin "T8") (pinfunction "A8_T8") (pintype "unspecified"))
    )
    (net (code "13") (name "A9") (class "Default")
      (node (ref "U4") (pin "E7") (pinfunction "DDR_A9_E7") (pintype "unspecified"))
      (node (ref "U7") (pin "R3") (pinfunction "A9_R3") (pintype "unspecified"))
    )
    (net (code "14") (name "A10") (class "Default")
      (node (ref "U4") (pin "C9") (pinfunction "DDR_A10_C9") (pintype "unspecified"))
      (node (ref "U7") (pin "L7") (pinfunction "A10/AP_L7") (pintype "unspecified"))
    )
    (net (code "15") (name "A11") (class "Default")
      (node (ref "U4") (pin "B5") (pinfunction "DDR_A11_B5") (pintype "unspecified"))
      (node (ref "U7") (pin "R7") (pinfunction "A11_R7") (pintype "unspecified"))
    )
    (net (code "16") (name "A12") (class "Default")
      (node (ref "U4") (pin "B6") (pinfunction "DDR_A12_B6") (pintype "unspecified"))
      (node (ref "U7") (pin "N7") (pinfunction "A12/BC#_N7") (pintype "unspecified"))
    )
    (net (code "17") (name "A13") (class "Default")
      (node (ref "U4") (pin "D7") (pinfunction "DDR_A13_D7") (pintype "unspecified"))
      (node (ref "U7") (pin "T3") (pinfunction "A13_T3") (pintype "unspecified"))
    )
    (net (code "18") (name "A14") (class "Default")
      (node (ref "U4") (pin "B10") (pinfunction "DDR_A14_B10") (pintype "unspecified"))
      (node (ref "U7") (pin "T7") (pinfunction "A14_T7") (pintype "unspecified"))
    )
    (net (code "19") (name "BA0") (class "Default")
      (node (ref "U4") (pin "B2") (pinfunction "DDR_BA0_B2") (pintype "unspecified"))
      (node (ref "U7") (pin "M2") (pinfunction "BA0_M2") (pintype "unspecified"))
    )
    (net (code "20") (name "BA1") (class "Default")
      (node (ref "U4") (pin "C8") (pinfunction "DDR_BA1_C8") (pintype "unspecified"))
      (node (ref "U7") (pin "N8") (pinfunction "BA1_N8") (pintype "unspecified"))
    )
    (net (code "21") (name "BA2") (class "Default")
      (node (ref "U4") (pin "D6") (pinfunction "DDR_BA2_D6") (pintype "unspecified"))
      (node (ref "U7") (pin "M3") (pinfunction "BA2_M3") (pintype "unspecified"))
    )
    (net (code "22") (name "CAS#") (class "Default")
      (node (ref "U4") (pin "D8") (pinfunction "DDR_CASN_D8") (pintype "unspecified"))
      (node (ref "U7") (pin "K3") (pinfunction "CAS#_K3") (pintype "unspecified"))
    )
    (net (code "23") (name "CKE") (class "Default")
      (node (ref "U4") (pin "B9") (pinfunction "DDR_CKE_B9") (pintype "unspecified"))
      (node (ref "U7") (pin "K9") (pinfunction "CKE_K9") (pintype "unspecified"))
    )
    (net (code "24") (name "CS#") (class "Default")
      (node (ref "U4") (pin "B1") (pinfunction "DDR_CS0N_B1") (pintype "unspecified"))
      (node (ref "U7") (pin "L2") (pinfunction "CS#_L2") (pintype "unspecified"))
    )
    (net (code "25") (name "D+") (class "Default")
      (node (ref "R17") (pin "1") (pinfunction "1_1") (pintype "input"))
      (node (ref "U11") (pin "5") (pinfunction "D+_5") (pintype "unspecified"))
      (node (ref "USB1") (pin "3") (pinfunction "D+_3") (pintype "input"))
    )
    (net (code "26") (name "D+1") (class "Default")
      (node (ref "R18") (pin "1") (pinfunction "1_1") (pintype "input"))
      (node (ref "USB2") (pin "3") (pinfunction "D+_3") (pintype "input"))
    )
    (net (code "27") (name "D-") (class "Default")
      (node (ref "R19") (pin "1") (pinfunction "1_1") (pintype "input"))
      (node (ref "U11") (pin "6") (pinfunction "D-_6") (pintype "unspecified"))
      (node (ref "USB1") (pin "2") (pinfunction "D-_2") (pintype "input"))
    )
    (net (code "28") (name "D-1") (class "Default")
      (node (ref "R20") (pin "1") (pinfunction "1_1") (pintype "input"))
      (node (ref "USB2") (pin "2") (pinfunction "D-_2") (pintype "input"))
    )
    (net (code "29") (name "DDR-CK") (class "Default")
      (node (ref "U4") (pin "C3") (pinfunction "DDR_CLK_C3") (pintype "unspecified"))
      (node (ref "U7") (pin "J7") (pinfunction "CK_J7") (pintype "unspecified"))
    )
    (net (code "30") (name "DDR-CK#") (class "Default")
      (node (ref "U4") (pin "C2") (pinfunction "DDR_CLKN_C2") (pintype "unspecified"))
      (node (ref "U7") (pin "K7") (pinfunction "CK#_K7") (pintype "unspecified"))
    )
    (net (code "31") (name "DML") (class "Default")
      (node (ref "U4") (pin "G1") (pinfunction "DDR_DM0_G1") (pintype "unspecified"))
      (node (ref "U7") (pin "E7") (pinfunction "DML_E7") (pintype "unspecified"))
    )
    (net (code "32") (name "DMU") (class "Default")
      (node (ref "U4") (pin "L3") (pinfunction "DDR_DM1_L3") (pintype "unspecified"))
      (node (ref "U7") (pin "D3") (pinfunction "DMU_D3") (pintype "unspecified"))
    )
    (net (code "33") (name "DQ0") (class "Default")
      (node (ref "U4") (pin "J4") (pinfunction "DDR_DQ0_J4") (pintype "unspecified"))
      (node (ref "U7") (pin "E3") (pinfunction "DQL0_E3") (pintype "unspecified"))
    )
    (net (code "34") (name "DQ1") (class "Default")
      (node (ref "U4") (pin "G5") (pinfunction "DDR_DQ1_G5") (pintype "unspecified"))
      (node (ref "U7") (pin "F7") (pinfunction "DQL1_F7") (pintype "unspecified"))
    )
    (net (code "35") (name "DQ2") (class "Default")
      (node (ref "U4") (pin "H4") (pinfunction "DDR_DQ2_H4") (pintype "unspecified"))
      (node (ref "U7") (pin "F2") (pinfunction "DQL2_F2") (pintype "unspecified"))
    )
    (net (code "36") (name "DQ3") (class "Default")
      (node (ref "U4") (pin "L1") (pinfunction "DDR_DQ3_L1") (pintype "unspecified"))
      (node (ref "U7") (pin "F8") (pinfunction "DQL3_F8") (pintype "unspecified"))
    )
    (net (code "37") (name "DQ4") (class "Default")
      (node (ref "U4") (pin "E2") (pinfunction "DDR_DQ4_E2") (pintype "unspecified"))
      (node (ref "U7") (pin "H3") (pinfunction "DQL4_H3") (pintype "unspecified"))
    )
    (net (code "38") (name "DQ5") (class "Default")
      (node (ref "U4") (pin "F1") (pinfunction "DDR_DQ5_F1") (pintype "unspecified"))
      (node (ref "U7") (pin "H8") (pinfunction "DQL5_H8") (pintype "unspecified"))
    )
    (net (code "39") (name "DQ6") (class "Default")
      (node (ref "U4") (pin "E3") (pinfunction "DDR_DQ6_E3") (pintype "unspecified"))
      (node (ref "U7") (pin "G2") (pinfunction "DQL6_G2") (pintype "unspecified"))
    )
    (net (code "40") (name "DQ7") (class "Default")
      (node (ref "U4") (pin "K2") (pinfunction "DDR_DQ7_K2") (pintype "unspecified"))
      (node (ref "U7") (pin "H7") (pinfunction "DQL7_H7") (pintype "unspecified"))
    )
    (net (code "41") (name "DQ8") (class "Default")
      (node (ref "U4") (pin "F4") (pinfunction "DDR_DQ8_F4") (pintype "unspecified"))
      (node (ref "U7") (pin "D7") (pinfunction "DQU0_D7") (pintype "unspecified"))
    )
    (net (code "42") (name "DQ9") (class "Default")
      (node (ref "U4") (pin "G2") (pinfunction "DDR_DQ9_G2") (pintype "unspecified"))
      (node (ref "U7") (pin "C3") (pinfunction "DQU1_C3") (pintype "unspecified"))
    )
    (net (code "43") (name "DQ10") (class "Default")
      (node (ref "U4") (pin "L4") (pinfunction "DDR_DQ10_L4") (pintype "unspecified"))
      (node (ref "U7") (pin "C8") (pinfunction "DQU2_C8") (pintype "unspecified"))
    )
    (net (code "44") (name "DQ11") (class "Default")
      (node (ref "U4") (pin "D3") (pinfunction "DDR_DQ11_D3") (pintype "unspecified"))
      (node (ref "U7") (pin "C2") (pinfunction "DQU3_C2") (pintype "unspecified"))
    )
    (net (code "45") (name "DQ12") (class "Default")
      (node (ref "U4") (pin "L2") (pinfunction "DDR_DQ12_L2") (pintype "unspecified"))
      (node (ref "U7") (pin "A7") (pinfunction "DQU4_A7") (pintype "unspecified"))
    )
    (net (code "46") (name "DQ13") (class "Default")
      (node (ref "U4") (pin "F3") (pinfunction "DDR-DQ13_F3") (pintype "unspecified"))
      (node (ref "U7") (pin "A2") (pinfunction "DQU5_A2") (pintype "unspecified"))
    )
    (net (code "47") (name "DQ14") (class "Default")
      (node (ref "U4") (pin "M2") (pinfunction "DDR_DQ14_M2") (pintype "unspecified"))
      (node (ref "U7") (pin "B8") (pinfunction "DQU6_B8") (pintype "unspecified"))
    )
    (net (code "48") (name "DQ15") (class "Default")
      (node (ref "U4") (pin "K5") (pinfunction "DDR_DQ15_K5") (pintype "input"))
      (node (ref "U7") (pin "A3") (pinfunction "DQU7_A3") (pintype "unspecified"))
    )
    (net (code "49") (name "DQSL") (class "Default")
      (node (ref "U4") (pin "J3") (pinfunction "DDR_DQS0_J3") (pintype "unspecified"))
      (node (ref "U7") (pin "F3") (pinfunction "DQSL_F3") (pintype "unspecified"))
    )
    (net (code "50") (name "DQSL#") (class "Default")
      (node (ref "U4") (pin "K4") (pinfunction "DDR_DQS0N_K4") (pintype "unspecified"))
      (node (ref "U7") (pin "G3") (pinfunction "DQSL#_G3") (pintype "unspecified"))
    )
    (net (code "51") (name "DQSU") (class "Default")
      (node (ref "U4") (pin "H2") (pinfunction "DDR_DQS1_H2") (pintype "unspecified"))
      (node (ref "U7") (pin "C7") (pinfunction "DQSU_C7") (pintype "unspecified"))
    )
    (net (code "52") (name "DQSU#") (class "Default")
      (node (ref "U4") (pin "H3") (pinfunction "DDR_DQS1N_H3") (pintype "unspecified"))
      (node (ref "U7") (pin "B7") (pinfunction "DQSU#_B7") (pintype "unspecified"))
    )
    (net (code "53") (name "GND") (class "Default")
      (node (ref "C1") (pin "2") (pinfunction "2_2") (pintype "input"))
      (node (ref "C11") (pin "1") (pinfunction "1_1") (pintype "unspecified"))
      (node (ref "C12") (pin "2") (pinfunction "2_2") (pintype "input"))
      (node (ref "C13") (pin "2") (pinfunction "2_2") (pintype "input"))
      (node (ref "C14") (pin "2") (pinfunction "2_2") (pintype "input"))
      (node (ref "C16") (pin "2") (pinfunction "2_2") (pintype "unspecified"))
      (node (ref "C17") (pin "2") (pinfunction "2_2") (pintype "input"))
      (node (ref "C18") (pin "2") (pinfunction "2_2") (pintype "input"))
      (node (ref "C2") (pin "2") (pinfunction "2_2") (pintype "input"))
      (node (ref "C21") (pin "1") (pinfunction "1_1") (pintype "input"))
      (node (ref "C23") (pin "2") (pinfunction "2_2") (pintype "input"))
      (node (ref "C24") (pin "1") (pinfunction "1_1") (pintype "input"))
      (node (ref "C25") (pin "2") (pinfunction "2_2") (pintype "input"))
      (node (ref "C26") (pin "1") (pinfunction "1_1") (pintype "unspecified"))
      (node (ref "C27") (pin "1") (pinfunction "1_1") (pintype "unspecified"))
      (node (ref "C28") (pin "1") (pinfunction "1_1") (pintype "unspecified"))
      (node (ref "C3") (pin "2") (pinfunction "2_2") (pintype "input"))
      (node (ref "C30") (pin "2") (pinfunction "2_2") (pintype "input"))
      (node (ref "C31") (pin "2") (pinfunction "2_2") (pintype "input"))
      (node (ref "C32") (pin "2") (pinfunction "2_2") (pintype "input"))
      (node (ref "C33") (pin "2") (pinfunction "2_2") (pintype "input"))
      (node (ref "C34") (pin "2") (pinfunction "2_2") (pintype "unspecified"))
      (node (ref "C35") (pin "2") (pinfunction "2_2") (pintype "input"))
      (node (ref "C36") (pin "2") (pinfunction "2_2") (pintype "input"))
      (node (ref "C37") (pin "2") (pinfunction "2_2") (pintype "input"))
      (node (ref "C38") (pin "2") (pinfunction "2_2") (pintype "input"))
      (node (ref "C39") (pin "2") (pinfunction "2_2") (pintype "unspecified"))
      (node (ref "C4") (pin "2") (pinfunction "2_2") (pintype "input"))
      (node (ref "C40") (pin "1") (pinfunction "1_1") (pintype "input"))
      (node (ref "C41") (pin "2") (pinfunction "2_2") (pintype "input"))
      (node (ref "C42") (pin "2") (pinfunction "2_2") (pintype "input"))
      (node (ref "C43") (pin "2") (pinfunction "2_2") (pintype "input"))
      (node (ref "C44") (pin "1") (pinfunction "1_1") (pintype "input"))
      (node (ref "C45") (pin "2") (pinfunction "2_2") (pintype "unspecified"))
      (node (ref "C46") (pin "1") (pinfunction "1_1") (pintype "input"))
      (node (ref "H1") (pin "14") (pinfunction "14_14") (pintype "input"))
      (node (ref "H1") (pin "20") (pinfunction "20_20") (pintype "input"))
      (node (ref "H1") (pin "25") (pinfunction "25_25") (pintype "input"))
      (node (ref "H1") (pin "30") (pinfunction "30_30") (pintype "input"))
      (node (ref "H1") (pin "34") (pinfunction "34_34") (pintype "input"))
      (node (ref "H1") (pin "39") (pinfunction "39_39") (pintype "input"))
      (node (ref "H1") (pin "6") (pinfunction "6_6") (pintype "input"))
      (node (ref "H1") (pin "9") (pinfunction "9_9") (pintype "input"))
      (node (ref "R13") (pin "1") (pinfunction "1_1") (pintype "input"))
      (node (ref "R15") (pin "1") (pinfunction "1_1") (pintype "input"))
      (node (ref "R31") (pin "1") (pinfunction "1_1") (pintype "input"))
      (node (ref "R32") (pin "1") (pinfunction "1_1") (pintype "input"))
      (node (ref "R37") (pin "1") (pinfunction "1_1") (pintype "input"))
      (node (ref "SW3") (pin "2") (pinfunction "2_2") (pintype "unspecified"))
      (node (ref "TF1") (pin "10") (pinfunction "GND_10") (pintype "unspecified"))
      (node (ref "TF1") (pin "11") (pinfunction "GND_11") (pintype "unspecified"))
      (node (ref "TF1") (pin "12") (pinfunction "GND_12") (pintype "unspecified"))
      (node (ref "TF1") (pin "13") (pinfunction "GND_13") (pintype "unspecified"))
      (node (ref "TF1") (pin "6") (pinfunction "VSS_6") (pintype "unspecified"))
      (node (ref "U11") (pin "1") (pinfunction "GND_1") (pintype "unspecified"))
      (node (ref "U12") (pin "39") (pinfunction "GND_39") (pintype "unspecified"))
      (node (ref "U12") (pin "49") (pinfunction "EP_49") (pintype "unspecified"))
      (node (ref "U14") (pin "2") (pinfunction "2_2") (pintype "input"))
      (node (ref "U2") (pin "7") (pinfunction "EH_7") (pintype "input"))
      (node (ref "U2") (pin "A12") (pinfunction "GND_A12") (pintype "input"))
      (node (ref "U2") (pin "B12") (pinfunction "GND_B12") (pintype "input"))
      (node (ref "U3") (pin "1") (pinfunction "GND_1") (pintype "unspecified"))
      (node (ref "U4") (pin "A20") (pinfunction "VSS_A20") (pintype "unspecified"))
      (node (ref "U4") (pin "A4") (pinfunction "VSS_A4") (pintype "unspecified"))
      (node (ref "U4") (pin "A9") (pinfunction "VSS_A9") (pintype "unspecified"))
      (node (ref "U4") (pin "B11") (pinfunction "VSS_B11") (pintype "unspecified"))
      (node (ref "U4") (pin "B8") (pinfunction "VSS_B8") (pintype "unspecified"))
      (node (ref "U4") (pin "C12") (pinfunction "USB_ID_C12") (pintype "unspecified"))
      (node (ref "U4") (pin "C4") (pinfunction "VSS_C4") (pintype "unspecified"))
      (node (ref "U4") (pin "C6") (pinfunction "VSS_C6") (pintype "unspecified"))
      (node (ref "U4") (pin "C7") (pinfunction "VSS_C7") (pintype "unspecified"))
      (node (ref "U4") (pin "D2") (pinfunction "VSS_D2") (pintype "unspecified"))
      (node (ref "U4") (pin "N13") (pinfunction "VSS_N13") (pintype "unspecified"))
      (node (ref "U5") (pin "1") (pinfunction "ADJ(GND)_1") (pintype "input"))
      (node (ref "U6") (pin "2") (pinfunction "GND_2") (pintype "unspecified"))
      (node (ref "U7") (pin "A9") (pinfunction "VSS_A9") (pintype "unspecified"))
      (node (ref "U7") (pin "B1") (pinfunction "VSSQ_B1") (pintype "unspecified"))
      (node (ref "U7") (pin "B3") (pinfunction "VSS_B3") (pintype "unspecified"))
      (node (ref "U7") (pin "B9") (pinfunction "VSSQ_B9") (pintype "unspecified"))
      (node (ref "U7") (pin "D1") (pinfunction "VSSQ_D1") (pintype "unspecified"))
      (node (ref "U7") (pin "D8") (pinfunction "VSSQ_D8") (pintype "unspecified"))
      (node (ref "U7") (pin "E1") (pinfunction "VSS_E1") (pintype "unspecified"))
      (node (ref "U7") (pin "E2") (pinfunction "VSSQ_E2") (pintype "unspecified"))
      (node (ref "U7") (pin "E8") (pinfunction "VSSQ_E8") (pintype "unspecified"))
      (node (ref "U7") (pin "F9") (pinfunction "VSSQ_F9") (pintype "unspecified"))
      (node (ref "U7") (pin "G1") (pinfunction "VSSQ_G1") (pintype "unspecified"))
      (node (ref "U7") (pin "G8") (pinfunction "VSS_G8") (pintype "unspecified"))
      (node (ref "U7") (pin "G9") (pinfunction "VSSQ_G9") (pintype "unspecified"))
      (node (ref "U7") (pin "J2") (pinfunction "VSS_J2") (pintype "unspecified"))
      (node (ref "U7") (pin "J8") (pinfunction "VSS_J8") (pintype "unspecified"))
      (node (ref "U7") (pin "M1") (pinfunction "VSS_M1") (pintype "unspecified"))
      (node (ref "U7") (pin "M9") (pinfunction "VSS_M9") (pintype "unspecified"))
      (node (ref "U7") (pin "P1") (pinfunction "VSS_P1") (pintype "unspecified"))
      (node (ref "U7") (pin "P9") (pinfunction "VSS_P9") (pintype "unspecified"))
      (node (ref "U7") (pin "T1") (pinfunction "VSS_T1") (pintype "unspecified"))
      (node (ref "U7") (pin "T9") (pinfunction "VSS_T9") (pintype "unspecified"))
      (node (ref "U8") (pin "1") (pinfunction "ADJ/GND_1") (pintype "unspecified"))
      (node (ref "USB1") (pin "4") (pinfunction "GND_4") (pintype "input"))
      (node (ref "USB1") (pin "5") (pinfunction "GND_5") (pintype "input"))
      (node (ref "USB1") (pin "6") (pinfunction "GND_6") (pintype "input"))
      (node (ref "USB2") (pin "4") (pinfunction "GND_4") (pintype "input"))
      (node (ref "USB2") (pin "5") (pinfunction "GND_5") (pintype "input"))
      (node (ref "USB2") (pin "6") (pinfunction "GND_6") (pintype "input"))
      (node (ref "X1") (pin "2") (pinfunction "GND_2") (pintype "input"))
      (node (ref "X1") (pin "4") (pinfunction "GND_4") (pintype "input"))
      (node (ref "X3") (pin "2") (pinfunction "GND_2") (pintype "unspecified"))
      (node (ref "X3") (pin "4") (pinfunction "GND_4") (pintype "unspecified"))
    )
    (net (code "54") (name "GPIO1_D0") (class "Default")
      (node (ref "H1") (pin "3") (pinfunction "3_3") (pintype "input"))
      (node (ref "R39") (pin "2") (pinfunction "2_2") (pintype "input"))
    )
    (net (code "55") (name "GPIO1_D1") (class "Default")
      (node (ref "H1") (pin "5") (pinfunction "5_5") (pintype "input"))
      (node (ref "R40") (pin "1") (pinfunction "1_1") (pintype "input"))
    )
    (net (code "56") (name "Net-(C24-Pad2)") (class "Default")
      (node (ref "C24") (pin "2") (pinfunction "2_2") (pintype "input"))
      (node (ref "R1") (pin "2") (pinfunction "2_2") (pintype "input"))
      (node (ref "SW2") (pin "1") (pinfunction "1_1") (pintype "unspecified"))
    )
    (net (code "57") (name "Net-(F1-Pad2)") (class "Default")
      (node (ref "F1") (pin "2") (pinfunction "2_2") (pintype "input"))
      (node (ref "U2") (pin "A9") (pinfunction "VBUS_A9") (pintype "input"))
      (node (ref "U2") (pin "B9") (pinfunction "VBUS_B9") (pintype "input"))
    )
    (net (code "58") (name "Net-(LED1-K)") (class "Default")
      (node (ref "LED1") (pin "1") (pinfunction "K_1") (pintype "unspecified"))
      (node (ref "R29") (pin "2") (pinfunction "2_2") (pintype "input"))
    )
    (net (code "59") (name "Net-(LED2-K)") (class "Default")
      (node (ref "LED2") (pin "2") (pinfunction "K_2") (pintype "unspecified"))
      (node (ref "R28") (pin "2") (pinfunction "2_2") (pintype "input"))
    )
    (net (code "60") (name "Net-(LED3-K)") (class "Default")
      (node (ref "LED3") (pin "2") (pinfunction "K_2") (pintype "unspecified"))
      (node (ref "R32") (pin "2") (pinfunction "2_2") (pintype "input"))
    )
    (net (code "61") (name "Net-(LED4-K)") (class "Default")
      (node (ref "LED4") (pin "1") (pinfunction "K_1") (pintype "unspecified"))
      (node (ref "R35") (pin "2") (pinfunction "2_2") (pintype "input"))
    )
    (net (code "62") (name "Net-(TF1-CD{slash}DAT3)") (class "Default")
      (node (ref "R3") (pin "2") (pinfunction "2_2") (pintype "input"))
      (node (ref "TF1") (pin "2") (pinfunction "CD/DAT3_2") (pintype "unspecified"))
    )
    (net (code "63") (name "Net-(TF1-CMD)") (class "Default")
      (node (ref "R4") (pin "2") (pinfunction "2_2") (pintype "input"))
      (node (ref "TF1") (pin "3") (pinfunction "CMD_3") (pintype "unspecified"))
    )
    (net (code "64") (name "Net-(TF1-DAT0)") (class "Default")
      (node (ref "R5") (pin "2") (pinfunction "2_2") (pintype "input"))
      (node (ref "TF1") (pin "7") (pinfunction "DAT0_7") (pintype "unspecified"))
    )
    (net (code "65") (name "Net-(TF1-DAT1)") (class "Default")
      (node (ref "R6") (pin "2") (pinfunction "2_2") (pintype "input"))
      (node (ref "TF1") (pin "8") (pinfunction "DAT1_8") (pintype "unspecified"))
    )
    (net (code "66") (name "Net-(TF1-DAT2)") (class "Default")
      (node (ref "R2") (pin "2") (pinfunction "2_2") (pintype "input"))
      (node (ref "TF1") (pin "1") (pinfunction "DAT2_1") (pintype "unspecified"))
    )
    (net (code "67") (name "Net-(U4A-GPIO0_A0)") (class "Default")
      (node (ref "R30") (pin "2") (pinfunction "2_2") (pintype "input"))
      (node (ref "U4") (pin "N3") (pinfunction "GPIO0_A0_N3") (pintype "unspecified"))
    )
    (net (code "68") (name "Net-(U4A-GPIO0_A1)") (class "Default")
      (node (ref "R31") (pin "2") (pinfunction "2_2") (pintype "input"))
      (node (ref "U4") (pin "N4") (pinfunction "GPIO0_A1_N4") (pintype "unspecified"))
    )
    (net (code "69") (name "Net-(U4A-NPOR)") (class "Default")
      (node (ref "SW2") (pin "2") (pinfunction "2_2") (pintype "unspecified"))
      (node (ref "U4") (pin "B20") (pinfunction "NPOR_B20") (pintype "unspecified"))
    )
    (net (code "70") (name "Net-(U4A-USB0_DM)") (class "Default")
      (node (ref "R19") (pin "2") (pinfunction "2_2") (pintype "input"))
      (node (ref "U4") (pin "A13") (pinfunction "USB0_DM_A13") (pintype "unspecified"))
    )
    (net (code "71") (name "Net-(U4A-USB0_DP)") (class "Default")
      (node (ref "R17") (pin "2") (pinfunction "2_2") (pintype "input"))
      (node (ref "U4") (pin "B13") (pinfunction "USB0_DP_B13") (pintype "unspecified"))
    )
    (net (code "72") (name "Net-(U4A-USB1_DM)") (class "Default")
      (node (ref "R20") (pin "2") (pinfunction "2_2") (pintype "input"))
      (node (ref "U4") (pin "A12") (pinfunction "USB1_DM_A12") (pintype "unspecified"))
    )
    (net (code "73") (name "Net-(U4A-USB1_DP)") (class "Default")
      (node (ref "R18") (pin "2") (pinfunction "2_2") (pintype "input"))
      (node (ref "U4") (pin "B12") (pinfunction "USB1_DP_B12") (pintype "unspecified"))
    )
    (net (code "74") (name "Net-(U4A-USB_EXTR)") (class "Default")
      (node (ref "R33") (pin "1") (pinfunction "1_1") (pintype "input"))
      (node (ref "U4") (pin "C15") (pinfunction "USB_EXTR_C15") (pintype "unspecified"))
    )
    (net (code "75") (name "Net-(U6-EN)") (class "Default")
      (node (ref "R38") (pin "1") (pinfunction "1_1") (pintype "input"))
      (node (ref "U6") (pin "3") (pinfunction "EN_3") (pintype "unspecified"))
    )
    (net (code "76") (name "Net-(U7-VREFCA)") (class "Default")
      (node (ref "R14") (pin "2") (pinfunction "2_2") (pintype "input"))
      (node (ref "R15") (pin "2") (pinfunction "2_2") (pintype "input"))
      (node (ref "U7") (pin "M8") (pinfunction "VREFCA_M8") (pintype "unspecified"))
    )
    (net (code "77") (name "Net-(U7-VREFDQ)") (class "Default")
      (node (ref "R36") (pin "1") (pinfunction "1_1") (pintype "input"))
      (node (ref "R37") (pin "2") (pinfunction "2_2") (pintype "input"))
      (node (ref "U7") (pin "H1") (pinfunction "VREFDQ_H1") (pintype "unspecified"))
    )
    (net (code "78") (name "Net-(U7-ZQ)") (class "Default")
      (node (ref "R13") (pin "2") (pinfunction "2_2") (pintype "input"))
      (node (ref "U7") (pin "L8") (pinfunction "ZQ_L8") (pintype "unspecified"))
    )
    (net (code "79") (name "Net-(U8-Fin)") (class "Default")
      (node (ref "C29") (pin "1") (pinfunction "1_1") (pintype "unspecified"))
      (node (ref "U8") (pin "4") (pinfunction "Fin_4") (pintype "unspecified"))
    )
    (net (code "80") (name "Net-(U12-BT_DIS#{slash}GPIO11)") (class "Default")
      (node (ref "R27") (pin "1") (pinfunction "1_1") (pintype "input"))
      (node (ref "U12") (pin "43") (pinfunction "BT_DIS#/GPIO11_43") (pintype "unspecified"))
    )
    (net (code "81") (name "Net-(U12-GPIO7{slash}BT_LED)") (class "Default")
      (node (ref "R29") (pin "1") (pinfunction "1_1") (pintype "input"))
      (node (ref "U12") (pin "42") (pinfunction "GPIO7/BT_LED_42") (pintype "unspecified"))
    )
    (net (code "82") (name "Net-(U12-GPIO8{slash}WL_LED)") (class "Default")
      (node (ref "R28") (pin "1") (pinfunction "1_1") (pintype "input"))
      (node (ref "U12") (pin "44") (pinfunction "GPIO8/WL_LED_44") (pintype "unspecified"))
    )
    (net (code "83") (name "Net-(U12-RFIO_BTG_S0)") (class "Default")
      (node (ref "U12") (pin "48") (pinfunction "RFIO_BTG_S0_48") (pintype "unspecified"))
      (node (ref "U14") (pin "1") (pinfunction "1_1") (pintype "input"))
    )
    (net (code "84") (name "Net-(U12-SD_CMD{slash}GSPI_DI)") (class "Default")
      (node (ref "R21") (pin "1") (pinfunction "1_1") (pintype "input"))
      (node (ref "U12") (pin "32") (pinfunction "SD_CMD/GSPI_DI_32") (pintype "unspecified"))
    )
    (net (code "85") (name "Net-(U12-SD_D0{slash}GSPI_DO)") (class "Default")
      (node (ref "R22") (pin "1") (pinfunction "1_1") (pintype "input"))
      (node (ref "U12") (pin "30") (pinfunction "SD_D0/GSPI_DO_30") (pintype "unspecified"))
    )
    (net (code "86") (name "Net-(U12-SD_D1{slash}GSPI_INT)") (class "Default")
      (node (ref "R23") (pin "1") (pinfunction "1_1") (pintype "input"))
      (node (ref "U12") (pin "29") (pinfunction "SD_D1/GSPI_INT_29") (pintype "unspecified"))
    )
    (net (code "87") (name "Net-(U12-SD_D2)") (class "Default")
      (node (ref "R25") (pin "1") (pinfunction "1_1") (pintype "input"))
      (node (ref "U12") (pin "34") (pinfunction "SD_D2_34") (pintype "unspecified"))
    )
    (net (code "88") (name "Net-(U12-SD_D3{slash}GSPI_CS#)") (class "Default")
      (node (ref "R24") (pin "1") (pinfunction "1_1") (pintype "input"))
      (node (ref "U12") (pin "33") (pinfunction "SD_D3/GSPI_CS#_33") (pintype "unspecified"))
    )
    (net (code "89") (name "Net-(U12-VD1P25)") (class "Default")
      (node (ref "C44") (pin "2") (pinfunction "2_2") (pintype "input"))
      (node (ref "U12") (pin "40") (pinfunction "VD1P25_40") (pintype "unspecified"))
    )
    (net (code "90") (name "Net-(U12-WL_DIS#{slash}GPIO9)") (class "Default")
      (node (ref "R26") (pin "2") (pinfunction "2_2") (pintype "input"))
      (node (ref "U12") (pin "4") (pinfunction "WL_DIS#/GPIO9_4") (pintype "unspecified"))
    )
    (net (code "91") (name "ODT") (class "Default")
      (node (ref "U4") (pin "C5") (pinfunction "DDR_ODT0_C5") (pintype "unspecified"))
      (node (ref "U7") (pin "K1") (pinfunction "ODT_K1") (pintype "unspecified"))
    )
    (net (code "92") (name "P3") (class "Default")
      (node (ref "H1") (pin "7") (pinfunction "7_7") (pintype "input"))
      (node (ref "R34") (pin "2") (pinfunction "2_2") (pintype "input"))
      (node (ref "SW3") (pin "1") (pinfunction "1_1") (pintype "unspecified"))
      (node (ref "U4") (pin "P3") (pinfunction "GPIO0_A2_P3") (pintype "unspecified"))
    )
    (net (code "93") (name "PP1") (class "Default")
      (node (ref "H1") (pin "22") (pinfunction "22_22") (pintype "input"))
      (node (ref "U4") (pin "W4") (pinfunction "GPIO1_A3_W4") (pintype "unspecified"))
    )
    (net (code "94") (name "PP2") (class "Default")
      (node (ref "H1") (pin "23") (pinfunction "23_23") (pintype "input"))
      (node (ref "U4") (pin "Y16") (pinfunction "GPIO2_A2_Y16") (pintype "unspecified"))
    )
    (net (code "95") (name "PP3") (class "Default")
      (node (ref "H1") (pin "24") (pinfunction "24_24") (pintype "input"))
      (node (ref "U4") (pin "W16") (pinfunction "GPIO2_A3_W16") (pintype "unspecified"))
    )
    (net (code "96") (name "PP4") (class "Default")
      (node (ref "H1") (pin "26") (pinfunction "26_26") (pintype "input"))
      (node (ref "U4") (pin "T15") (pinfunction "GPIO2_A4_T15") (pintype "unspecified"))
    )
    (net (code "97") (name "PP5") (class "Default")
      (node (ref "H1") (pin "27") (pinfunction "27_27") (pintype "input"))
      (node (ref "U4") (pin "R16") (pinfunction "GPIO2_B0_R16") (pintype "unspecified"))
    )
    (net (code "98") (name "PP6") (class "Default")
      (node (ref "H1") (pin "28") (pinfunction "28_28") (pintype "input"))
      (node (ref "U4") (pin "V14") (pinfunction "GPIO2_B1_V14") (pintype "unspecified"))
    )
    (net (code "99") (name "PP7") (class "Default")
      (node (ref "H1") (pin "29") (pinfunction "29_29") (pintype "input"))
      (node (ref "U4") (pin "J15") (pinfunction "GPIO2_B2_J15") (pintype "unspecified"))
    )
    (net (code "100") (name "PP8") (class "Default")
      (node (ref "H1") (pin "31") (pinfunction "31_31") (pintype "input"))
      (node (ref "U4") (pin "U16") (pinfunction "GPIO2_B3_U16") (pintype "unspecified"))
    )
    (net (code "101") (name "PP9") (class "Default")
      (node (ref "H1") (pin "32") (pinfunction "32_32") (pintype "input"))
      (node (ref "U4") (pin "K16") (pinfunction "GPIO2_A4_K16") (pintype "unspecified"))
    )
    (net (code "102") (name "PP10") (class "Default")
      (node (ref "H1") (pin "33") (pinfunction "33_33") (pintype "input"))
      (node (ref "U4") (pin "R15") (pinfunction "GPIO2_A5_R15") (pintype "unspecified"))
    )
    (net (code "103") (name "PP11") (class "Default")
      (node (ref "H1") (pin "35") (pinfunction "35_35") (pintype "input"))
      (node (ref "U4") (pin "F17") (pinfunction "GPIO4_B0_F17") (pintype "unspecified"))
    )
    (net (code "104") (name "PP12") (class "Default")
      (node (ref "H1") (pin "36") (pinfunction "36_36") (pintype "input"))
      (node (ref "U4") (pin "J16") (pinfunction "GPIO4_B1_J16") (pintype "unspecified"))
    )
    (net (code "105") (name "PP13") (class "Default")
      (node (ref "H1") (pin "37") (pinfunction "37_37") (pintype "input"))
      (node (ref "U4") (pin "G16") (pinfunction "GPIO4_B2_G16") (pintype "unspecified"))
    )
    (net (code "106") (name "PP14") (class "Default")
      (node (ref "H1") (pin "38") (pinfunction "38_38") (pintype "input"))
      (node (ref "U4") (pin "F19") (pinfunction "GPIO4_B3_F19") (pintype "unspecified"))
    )
    (net (code "107") (name "PP15") (class "Default")
      (node (ref "H1") (pin "40") (pinfunction "40_40") (pintype "input"))
      (node (ref "U4") (pin "H16") (pinfunction "GPIO4_B4_H16") (pintype "unspecified"))
    )
    (net (code "108") (name "RAS#") (class "Default")
      (node (ref "U4") (pin "D5") (pinfunction "DDR_RASN_D5") (pintype "unspecified"))
      (node (ref "U7") (pin "J3") (pinfunction "RAS#_J3") (pintype "unspecified"))
    )
    (net (code "109") (name "RESET#") (class "Default")
      (node (ref "U4") (pin "E4") (pinfunction "DDR_RESET_E4") (pintype "unspecified"))
      (node (ref "U7") (pin "T2") (pinfunction "RESET#_T2") (pintype "unspecified"))
    )
    (net (code "110") (name "RXD") (class "Default")
      (node (ref "R3") (pin "1") (pinfunction "1_1") (pintype "input"))
      (node (ref "U11") (pin "3") (pinfunction "RXD_3") (pintype "unspecified"))
      (node (ref "U4") (pin "A15") (pinfunction "GPIO4_D3/SDMMC_D3/UART2_TX_M1_A15") (pintype "unspecified"))
    )
    (net (code "111") (name "SD3") (class "Default")
      (node (ref "R4") (pin "1") (pinfunction "1_1") (pintype "input"))
      (node (ref "U4") (pin "C16") (pinfunction "GPIO4_D4/SDMMC_CMD_C16") (pintype "unspecified"))
    )
    (net (code "112") (name "SD4") (class "Default")
      (node (ref "TF1") (pin "5") (pinfunction "CLK_5") (pintype "unspecified"))
      (node (ref "U4") (pin "B16") (pinfunction "GPIO4_D5/SDMMC_CLK_B16") (pintype "unspecified"))
    )
    (net (code "113") (name "SD5") (class "Default")
      (node (ref "R5") (pin "1") (pinfunction "1_1") (pintype "input"))
      (node (ref "U4") (pin "B17") (pinfunction "GPIO4_D0/SDMMC_D0_B17") (pintype "unspecified"))
    )
    (net (code "114") (name "SD6") (class "Default")
      (node (ref "R6") (pin "1") (pinfunction "1_1") (pintype "input"))
      (node (ref "U4") (pin "A17") (pinfunction "GPIO4_D1/SDMMC_D1_A17") (pintype "unspecified"))
    )
    (net (code "115") (name "SD7") (class "Default")
      (node (ref "TF1") (pin "9") (pinfunction "CD_9") (pintype "unspecified"))
      (node (ref "U4") (pin "P4") (pinfunction "SDMMC_DET_P4") (pintype "unspecified"))
    )
    (net (code "116") (name "SDIO_CLK") (class "Default")
      (node (ref "U12") (pin "31") (pinfunction "SD_CLK/GSPI_CLK_31") (pintype "unspecified"))
      (node (ref "U4") (pin "J18") (pinfunction "SDIO_CLK_J18") (pintype "unspecified"))
    )
    (net (code "117") (name "SDIO_CMD") (class "Default")
      (node (ref "R21") (pin "2") (pinfunction "2_2") (pintype "input"))
      (node (ref "U4") (pin "H18") (pinfunction "SDIO_CMD_H18") (pintype "unspecified"))
    )
    (net (code "118") (name "SDIO_D0") (class "Default")
      (node (ref "R22") (pin "2") (pinfunction "2_2") (pintype "input"))
      (node (ref "U4") (pin "J19") (pinfunction "SDIO_D0_J19") (pintype "unspecified"))
    )
    (net (code "119") (name "SDIO_D1") (class "Default")
      (node (ref "R23") (pin "2") (pinfunction "2_2") (pintype "input"))
      (node (ref "U4") (pin "J17") (pinfunction "SDIO_D1_J17") (pintype "unspecified"))
    )
    (net (code "120") (name "SDIO_D2") (class "Default")
      (node (ref "R25") (pin "2") (pinfunction "2_2") (pintype "input"))
      (node (ref "U4") (pin "G18") (pinfunction "SDIO_D2_G18") (pintype "unspecified"))
    )
    (net (code "121") (name "SDIO_D3") (class "Default")
      (node (ref "R24") (pin "2") (pinfunction "2_2") (pintype "input"))
      (node (ref "U4") (pin "G17") (pinfunction "SDIO_D3_G17") (pintype "unspecified"))
    )
    (net (code "122") (name "T1") (class "Default")
      (node (ref "H1") (pin "13") (pinfunction "13_13") (pintype "input"))
      (node (ref "U4") (pin "T1") (pinfunction "GPIO0_C1_T1") (pintype "unspecified"))
    )
    (net (code "123") (name "TXD") (class "Default")
      (node (ref "R2") (pin "1") (pinfunction "1_1") (pintype "input"))
      (node (ref "U11") (pin "2") (pinfunction "TXD_2") (pintype "unspecified"))
      (node (ref "U4") (pin "B15") (pinfunction "GPIO4_D2/SDMMC_D2/UART2_RX_M1_B15") (pintype "unspecified"))
    )
    (net (code "124") (name "U2") (class "Default")
      (node (ref "H1") (pin "12") (pinfunction "12_12") (pintype "input"))
      (node (ref "U4") (pin "U2") (pinfunction "GPIO0_C0_U2") (pintype "unspecified"))
    )
    (net (code "125") (name "U4") (class "Default")
      (node (ref "H1") (pin "18") (pinfunction "18_18") (pintype "input"))
      (node (ref "U4") (pin "U4") (pinfunction "GPIO1_A2/LCDC_VSYNC/I2S1_8CH_MCLK_M0_U4") (pintype "unspecified"))
    )
    (net (code "126") (name "U14") (class "Default")
      (node (ref "H1") (pin "10") (pinfunction "10_10") (pintype "input"))
      (node (ref "H1") (pin "21") (pinfunction "21_21") (pintype "input"))
      (node (ref "U4") (pin "U14") (pinfunction "UART0_RX_U14") (pintype "unspecified"))
    )
    (net (code "127") (name "V3") (class "Default")
      (node (ref "H1") (pin "11") (pinfunction "11_11") (pintype "input"))
      (node (ref "R35") (pin "1") (pinfunction "1_1") (pintype "input"))
      (node (ref "U4") (pin "V3") (pinfunction "GPIO0_B5_V3") (pintype "unspecified"))
    )
    (net (code "128") (name "V4") (class "Default")
      (node (ref "H1") (pin "16") (pinfunction "16_16") (pintype "input"))
      (node (ref "U4") (pin "V4") (pinfunction "GPIO1_A1_V4") (pintype "unspecified"))
    )
    (net (code "129") (name "V16") (class "Default")
      (node (ref "H1") (pin "19") (pinfunction "19_19") (pintype "input"))
      (node (ref "H1") (pin "8") (pinfunction "8_8") (pintype "input"))
      (node (ref "U4") (pin "V16") (pinfunction "UART0_TX_V16") (pintype "unspecified"))
    )
    (net (code "130") (name "VBUS") (class "Default")
      (node (ref "C45") (pin "1") (pinfunction "1_1") (pintype "unspecified"))
      (node (ref "C46") (pin "2") (pinfunction "2_2") (pintype "input"))
      (node (ref "F1") (pin "1") (pinfunction "1_1") (pintype "input"))
      (node (ref "H1") (pin "2") (pinfunction "2_2") (pintype "input"))
      (node (ref "H1") (pin "4") (pinfunction "4_4") (pintype "input"))
      (node (ref "U3") (pin "3") (pinfunction "VIN_3") (pintype "unspecified"))
      (node (ref "U4") (pin "C14") (pinfunction "USB_VBUS_C14") (pintype "unspecified"))
      (node (ref "USB1") (pin "1") (pinfunction "VBUS_1") (pintype "input"))
      (node (ref "USB2") (pin "1") (pinfunction "VBUS_1") (pintype "input"))
    )
    (net (code "131") (name "VCC") (class "Default")
      (node (ref "C1") (pin "1") (pinfunction "1_1") (pintype "input"))
      (node (ref "C11") (pin "2") (pinfunction "2_2") (pintype "unspecified"))
      (node (ref "C18") (pin "1") (pinfunction "1_1") (pintype "input"))
      (node (ref "C25") (pin "1") (pinfunction "1_1") (pintype "input"))
      (node (ref "C26") (pin "2") (pinfunction "2_2") (pintype "unspecified"))
      (node (ref "C27") (pin "2") (pinfunction "2_2") (pintype "unspecified"))
      (node (ref "C29") (pin "2") (pinfunction "2_2") (pintype "unspecified"))
      (node (ref "C3") (pin "1") (pinfunction "1_1") (pintype "input"))
      (node (ref "C35") (pin "1") (pinfunction "1_1") (pintype "input"))
      (node (ref "C36") (pin "1") (pinfunction "1_1") (pintype "input"))
      (node (ref "C37") (pin "1") (pinfunction "1_1") (pintype "input"))
      (node (ref "C38") (pin "1") (pinfunction "1_1") (pintype "input"))
      (node (ref "C39") (pin "1") (pinfunction "1_1") (pintype "unspecified"))
      (node (ref "C4") (pin "1") (pinfunction "1_1") (pintype "input"))
      (node (ref "H1") (pin "1") (pinfunction "1_1") (pintype "input"))
      (node (ref "H1") (pin "17") (pinfunction "17_17") (pintype "input"))
      (node (ref "LED1") (pin "2") (pinfunction "A_2") (pintype "unspecified"))
      (node (ref "LED2") (pin "1") (pinfunction "A_1") (pintype "unspecified"))
      (node (ref "LED3") (pin "1") (pinfunction "A_1") (pintype "unspecified"))
      (node (ref "LED4") (pin "2") (pinfunction "A_2") (pintype "unspecified"))
      (node (ref "R1") (pin "1") (pinfunction "1_1") (pintype "input"))
      (node (ref "R26") (pin "1") (pinfunction "1_1") (pintype "input"))
      (node (ref "R27") (pin "2") (pinfunction "2_2") (pintype "input"))
      (node (ref "R30") (pin "1") (pinfunction "1_1") (pintype "input"))
      (node (ref "R33") (pin "2") (pinfunction "2_2") (pintype "input"))
      (node (ref "R34") (pin "1") (pinfunction "1_1") (pintype "input"))
      (node (ref "R38") (pin "2") (pinfunction "2_2") (pintype "input"))
      (node (ref "TF1") (pin "4") (pinfunction "VDD_4") (pintype "unspecified"))
      (node (ref "U11") (pin "16") (pinfunction "VCC_16") (pintype "unspecified"))
      (node (ref "U12") (pin "28") (pinfunction "VDD_IO_28") (pintype "unspecified"))
      (node (ref "U12") (pin "41") (pinfunction "VD33D_41") (pintype "unspecified"))
      (node (ref "U3") (pin "2") (pinfunction "VOUT_2") (pintype "unspecified"))
      (node (ref "U3") (pin "4") (pinfunction "VOUT_4") (pintype "unspecified"))
      (node (ref "U4") (pin "D13") (pinfunction "USB_AVDD_3V3_D13") (pintype "unspecified"))
      (node (ref "U4") (pin "D14") (pinfunction "VCCIO5_D14") (pintype "unspecified"))
      (node (ref "U4") (pin "E14") (pinfunction "USB_AVDD_3V3_E14") (pintype "unspecified"))
      (node (ref "U5") (pin "3") (pinfunction "VIN_3") (pintype "input"))
      (node (ref "U6") (pin "1") (pinfunction "VIN_1") (pintype "unspecified"))
      (node (ref "U8") (pin "3") (pinfunction "VIN_3") (pintype "unspecified"))
    )
    (net (code "132") (name "WE#") (class "Default")
      (node (ref "U4") (pin "E8") (pinfunction "DDR_WEN_E8") (pintype "unspecified"))
      (node (ref "U7") (pin "L3") (pinfunction "WE#_L3") (pintype "unspecified"))
    )
    (net (code "133") (name "WRX") (class "Default")
      (node (ref "R39") (pin "1") (pinfunction "1_1") (pintype "input"))
      (node (ref "U12") (pin "27") (pinfunction "UART_OUT_27") (pintype "unspecified"))
      (node (ref "U4") (pin "V10") (pinfunction "UART1_RX_V10") (pintype "unspecified"))
    )
    (net (code "134") (name "WTX") (class "Default")
      (node (ref "R40") (pin "2") (pinfunction "2_2") (pintype "input"))
      (node (ref "U12") (pin "25") (pinfunction "UART_IN_25") (pintype "unspecified"))
      (node (ref "U4") (pin "T10") (pinfunction "UART1_TX_T10") (pintype "unspecified"))
    )
    (net (code "135") (name "XI") (class "Default")
      (node (ref "C41") (pin "1") (pinfunction "1_1") (pintype "input"))
      (node (ref "U12") (pin "15") (pinfunction "XI_15") (pintype "unspecified"))
      (node (ref "X3") (pin "1") (pinfunction "OSC1_1") (pintype "unspecified"))
    )
    (net (code "136") (name "XIN") (class "Default")
      (node (ref "C23") (pin "1") (pinfunction "1_1") (pintype "input"))
      (node (ref "U4") (pin "E19") (pinfunction "XIN_24M_E19") (pintype "unspecified"))
      (node (ref "X1") (pin "1") (pinfunction "1_1") (pintype "input"))
    )
    (net (code "137") (name "XO") (class "Default")
      (node (ref "C40") (pin "2") (pinfunction "2_2") (pintype "input"))
      (node (ref "U12") (pin "16") (pinfunction "XO_16") (pintype "unspecified"))
      (node (ref "X3") (pin "3") (pinfunction "OSC2_3") (pintype "unspecified"))
    )
    (net (code "138") (name "XOUT") (class "Default")
      (node (ref "C21") (pin "2") (pinfunction "2_2") (pintype "input"))
      (node (ref "U4") (pin "E20") (pinfunction "XOUT_24M_E20") (pintype "unspecified"))
      (node (ref "X1") (pin "3") (pinfunction "3_3") (pintype "input"))
    )
    (net (code "139") (name "Y5") (class "Default")
      (node (ref "H1") (pin "15") (pinfunction "15_15") (pintype "input"))
      (node (ref "U4") (pin "Y5") (pinfunction "GPIO1_A0_Y5") (pintype "unspecified"))
    )
    (net (code "140") (name "unconnected-(U2-CC1-PadA5)") (class "Default")
      (node (ref "U2") (pin "A5") (pinfunction "CC1_A5") (pintype "input+no_connect"))
    )
    (net (code "141") (name "unconnected-(U2-CC2-PadB5)") (class "Default")
      (node (ref "U2") (pin "B5") (pinfunction "CC2_B5") (pintype "input+no_connect"))
    )
    (net (code "142") (name "unconnected-(U4A-ADC_IN0-PadA19)") (class "Default")
      (node (ref "U4") (pin "A19") (pinfunction "ADC_IN0_A19") (pintype "unspecified+no_connect"))
    )
    (net (code "143") (name "unconnected-(U4A-ADC_IN1-PadB19)") (class "Default")
      (node (ref "U4") (pin "B19") (pinfunction "ADC_IN1_B19") (pintype "unspecified+no_connect"))
    )
    (net (code "144") (name "unconnected-(U4A-ADC_IN3-PadA18)") (class "Default")
      (node (ref "U4") (pin "A18") (pinfunction "ADC_IN3_A18") (pintype "unspecified+no_connect"))
    )
    (net (code "145") (name "unconnected-(U4A-ADC_IN4-PadB18)") (class "Default")
      (node (ref "U4") (pin "B18") (pinfunction "ADC_IN4_B18") (pintype "unspecified+no_connect"))
    )
    (net (code "146") (name "unconnected-(U4A-GPIO4_D6{slash}SDMMC_PWREN-PadB14)") (class "Default")
      (node (ref "U4") (pin "B14") (pinfunction "GPIO4_D6/SDMMC_PWREN_B14") (pintype "unspecified+no_connect"))
    )
    (net (code "147") (name "unconnected-(U4A-VSS-PadE5)") (class "Default")
      (node (ref "U4") (pin "E5") (pinfunction "VSS_E5") (pintype "unspecified"))
    )
    (net (code "148") (name "unconnected-(U6-FB-Pad4)") (class "Default")
      (node (ref "U6") (pin "4") (pinfunction "FB_4") (pintype "unspecified+no_connect"))
    )
    (net (code "149") (name "unconnected-(U7-NC-PadJ1)") (class "Default")
      (node (ref "U7") (pin "J1") (pinfunction "NC_J1") (pintype "unspecified+no_connect"))
    )
    (net (code "150") (name "unconnected-(U7-NC-PadJ9)") (class "Default")
      (node (ref "U7") (pin "J9") (pinfunction "NC_J9") (pintype "unspecified+no_connect"))
    )
    (net (code "151") (name "unconnected-(U7-NC-PadL1)") (class "Default")
      (node (ref "U7") (pin "L1") (pinfunction "NC_L1") (pintype "unspecified+no_connect"))
    )
    (net (code "152") (name "unconnected-(U7-NC-PadL9)") (class "Default")
      (node (ref "U7") (pin "L9") (pinfunction "NC_L9") (pintype "unspecified+no_connect"))
    )
    (net (code "153") (name "unconnected-(U7-NC-PadM7)") (class "Default")
      (node (ref "U7") (pin "M7") (pinfunction "NC_M7") (pintype "unspecified+no_connect"))
    )
    (net (code "154") (name "unconnected-(U11-CTS#-Pad9)") (class "Default")
      (node (ref "U11") (pin "9") (pinfunction "CTS#_9") (pintype "unspecified+no_connect"))
    )
    (net (code "155") (name "unconnected-(U11-DCD#-Pad12)") (class "Default")
      (node (ref "U11") (pin "12") (pinfunction "DCD#_12") (pintype "unspecified+no_connect"))
    )
    (net (code "156") (name "unconnected-(U11-DSR#-Pad10)") (class "Default")
      (node (ref "U11") (pin "10") (pinfunction "DSR#_10") (pintype "unspecified+no_connect"))
    )
    (net (code "157") (name "unconnected-(U11-DTR#-Pad13)") (class "Default")
      (node (ref "U11") (pin "13") (pinfunction "DTR#_13") (pintype "unspecified+no_connect"))
    )
    (net (code "158") (name "unconnected-(U11-NC.-Pad7)") (class "Default")
      (node (ref "U11") (pin "7") (pinfunction "NC._7") (pintype "unspecified+no_connect"))
    )
    (net (code "159") (name "unconnected-(U11-OUT#-Pad8)") (class "Default")
      (node (ref "U11") (pin "8") (pinfunction "OUT#_8") (pintype "unspecified+no_connect"))
    )
    (net (code "160") (name "unconnected-(U11-R232-Pad15)") (class "Default")
      (node (ref "U11") (pin "15") (pinfunction "R232_15") (pintype "unspecified+no_connect"))
    )
    (net (code "161") (name "unconnected-(U11-RI#-Pad11)") (class "Default")
      (node (ref "U11") (pin "11") (pinfunction "RI#_11") (pintype "unspecified+no_connect"))
    )
    (net (code "162") (name "unconnected-(U11-RTS#-Pad14)") (class "Default")
      (node (ref "U11") (pin "14") (pinfunction "RTS#_14") (pintype "unspecified+no_connect"))
    )
    (net (code "163") (name "unconnected-(U11-V3-Pad4)") (class "Default")
      (node (ref "U11") (pin "4") (pinfunction "V3_4") (pintype "unspecified+no_connect"))
    )
    (net (code "164") (name "unconnected-(U12-EEPROM_SEL{slash}GPIO12-Pad17)") (class "Default")
      (node (ref "U12") (pin "17") (pinfunction "EEPROM_SEL/GPIO12_17") (pintype "unspecified+no_connect"))
    )
    (net (code "165") (name "unconnected-(U12-GPIO0-Pad21)") (class "Default")
      (node (ref "U12") (pin "21") (pinfunction "GPIO0_21") (pintype "unspecified+no_connect"))
    )
    (net (code "166") (name "unconnected-(U12-GPIO2-Pad23)") (class "Default")
      (node (ref "U12") (pin "23") (pinfunction "GPIO2_23") (pintype "unspecified+no_connect"))
    )
    (net (code "167") (name "unconnected-(U12-GPIO3-Pad24)") (class "Default")
      (node (ref "U12") (pin "24") (pinfunction "GPIO3_24") (pintype "unspecified+no_connect"))
    )
    (net (code "168") (name "unconnected-(U12-GPIO4-Pad46)") (class "Default")
      (node (ref "U12") (pin "46") (pinfunction "GPIO4_46") (pintype "unspecified+no_connect"))
    )
    (net (code "169") (name "unconnected-(U12-GPIO5-Pad45)") (class "Default")
      (node (ref "U12") (pin "45") (pinfunction "GPIO5_45") (pintype "unspecified+no_connect"))
    )
    (net (code "170") (name "unconnected-(U12-GPIO6-Pad20)") (class "Default")
      (node (ref "U12") (pin "20") (pinfunction "GPIO6_20") (pintype "unspecified+no_connect"))
    )
    (net (code "171") (name "unconnected-(U12-GPIO13-Pad18)") (class "Default")
      (node (ref "U12") (pin "18") (pinfunction "GPIO13_18") (pintype "unspecified+no_connect"))
    )
    (net (code "172") (name "unconnected-(U12-GPIO15-Pad47)") (class "Default")
      (node (ref "U12") (pin "47") (pinfunction "GPIO15_47") (pintype "unspecified+no_connect"))
    )
    (net (code "173") (name "unconnected-(U12-RFIO_BTG_S1-Pad11)") (class "Default")
      (node (ref "U12") (pin "11") (pinfunction "RFIO_BTG_S1_11") (pintype "unspecified+no_connect"))
    )
    (net (code "174") (name "unconnected-(U12-SPS_LDO_SEL{slash}GPIO1-Pad22)") (class "Default")
      (node (ref "U12") (pin "22") (pinfunction "SPS_LDO_SEL/GPIO1_22") (pintype "unspecified+no_connect"))
    )
    (net (code "175") (name "unconnected-(U12-SW_GND-Pad35)") (class "Default")
      (node (ref "U12") (pin "35") (pinfunction "SW_GND_35") (pintype "unspecified+no_connect"))
    )
    (net (code "176") (name "unconnected-(U12-SW_LX-Pad36)") (class "Default")
      (node (ref "U12") (pin "36") (pinfunction "SW_LX_36") (pintype "unspecified+no_connect"))
    )
    (net (code "177") (name "unconnected-(U12-TEST_MOD_SEL{slash}GPIO14-Pad19)") (class "Default")
      (node (ref "U12") (pin "19") (pinfunction "TEST_MOD_SEL/GPIO14_19") (pintype "unspecified+no_connect"))
    )
    (net (code "178") (name "unconnected-(U12-UART_CTS-Pad26)") (class "Default")
      (node (ref "U12") (pin "26") (pinfunction "UART_CTS_26") (pintype "unspecified+no_connect"))
    )
    (net (code "179") (name "unconnected-(U12-VA1P25_AFE-Pad13)") (class "Default")
      (node (ref "U12") (pin "13") (pinfunction "VA1P25_AFE_13") (pintype "unspecified+no_connect"))
    )
    (net (code "180") (name "unconnected-(U12-VA1P25_BT_SYN-Pad5)") (class "Default")
      (node (ref "U12") (pin "5") (pinfunction "VA1P25_BT_SYN_5") (pintype "unspecified+no_connect"))
    )
    (net (code "181") (name "unconnected-(U12-VA1P25_RTX_S0-Pad3)") (class "Default")
      (node (ref "U12") (pin "3") (pinfunction "VA1P25_RTX_S0_3") (pintype "unspecified+no_connect"))
    )
    (net (code "182") (name "unconnected-(U12-VA1P25_RTX_S1-Pad9)") (class "Default")
      (node (ref "U12") (pin "9") (pinfunction "VA1P25_RTX_S1_9") (pintype "unspecified+no_connect"))
    )
    (net (code "183") (name "unconnected-(U12-VA1P25_WL_SYN-Pad8)") (class "Default")
      (node (ref "U12") (pin "8") (pinfunction "VA1P25_WL_SYN_8") (pintype "unspecified+no_connect"))
    )
    (net (code "184") (name "unconnected-(U12-VA33_AFE-Pad14)") (class "Default")
      (node (ref "U12") (pin "14") (pinfunction "VA33_AFE_14") (pintype "unspecified+no_connect"))
    )
    (net (code "185") (name "unconnected-(U12-VA33_BT_SYN-Pad6)") (class "Default")
      (node (ref "U12") (pin "6") (pinfunction "VA33_BT_SYN_6") (pintype "unspecified+no_connect"))
    )
    (net (code "186") (name "unconnected-(U12-VA33_PAD_S0-Pad2)") (class "Default")
      (node (ref "U12") (pin "2") (pinfunction "VA33_PAD_S0_2") (pintype "unspecified+no_connect"))
    )
    (net (code "187") (name "unconnected-(U12-VA33_PAD_S1-Pad10)") (class "Default")
      (node (ref "U12") (pin "10") (pinfunction "VA33_PAD_S1_10") (pintype "unspecified+no_connect"))
    )
    (net (code "188") (name "unconnected-(U12-VA33_PA_S0-Pad1)") (class "Default")
      (node (ref "U12") (pin "1") (pinfunction "VA33_PA_S0_1") (pintype "unspecified+no_connect"))
    )
    (net (code "189") (name "unconnected-(U12-VA33_PA_S1-Pad12)") (class "Default")
      (node (ref "U12") (pin "12") (pinfunction "VA33_PA_S1_12") (pintype "unspecified+no_connect"))
    )
    (net (code "190") (name "unconnected-(U12-VA33_WL_SYN-Pad7)") (class "Default")
      (node (ref "U12") (pin "7") (pinfunction "VA33_WL_SYN_7") (pintype "unspecified+no_connect"))
    )
    (net (code "191") (name "unconnected-(U12-VD33D-Pad37)") (class "Default")
      (node (ref "U12") (pin "37") (pinfunction "VD33D_37") (pintype "unspecified+no_connect"))
    )
    (net (code "192") (name "unconnected-(U12-VD33D-Pad38)") (class "Default")
      (node (ref "U12") (pin "38") (pinfunction "VD33D_38") (pintype "unspecified+no_connect"))
    )
  )
)
